# HeadNode_V2.net
KiCad netlist of a schematic drawn in EAGLE
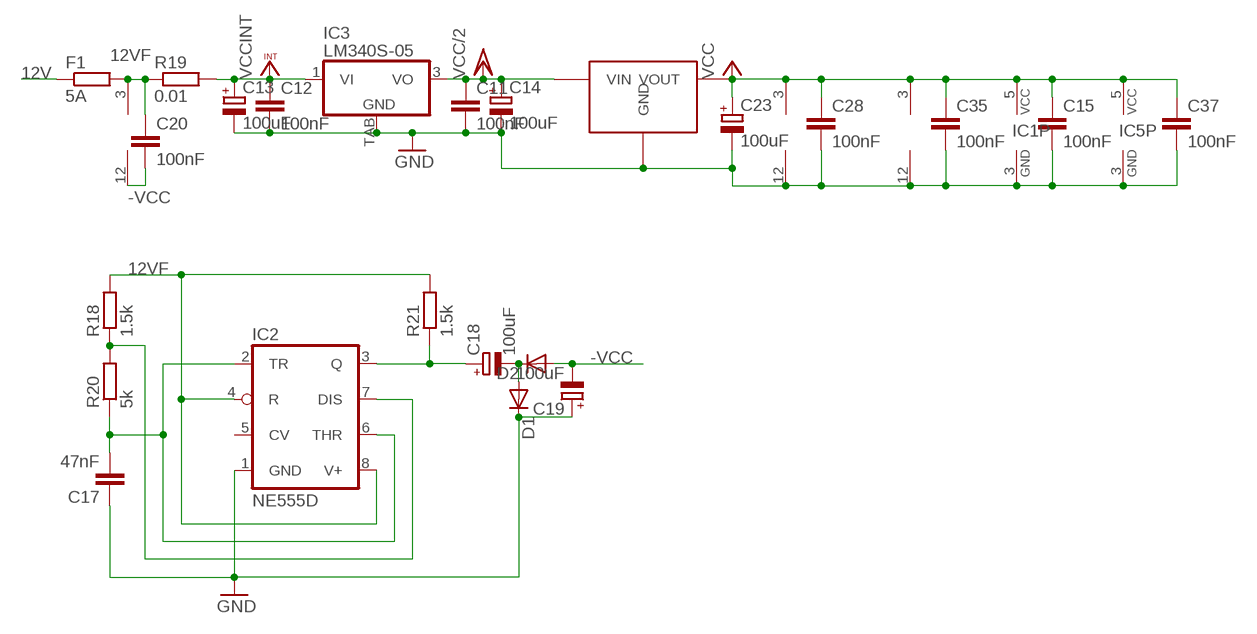
[diagram p0: schematic, sheet 1]
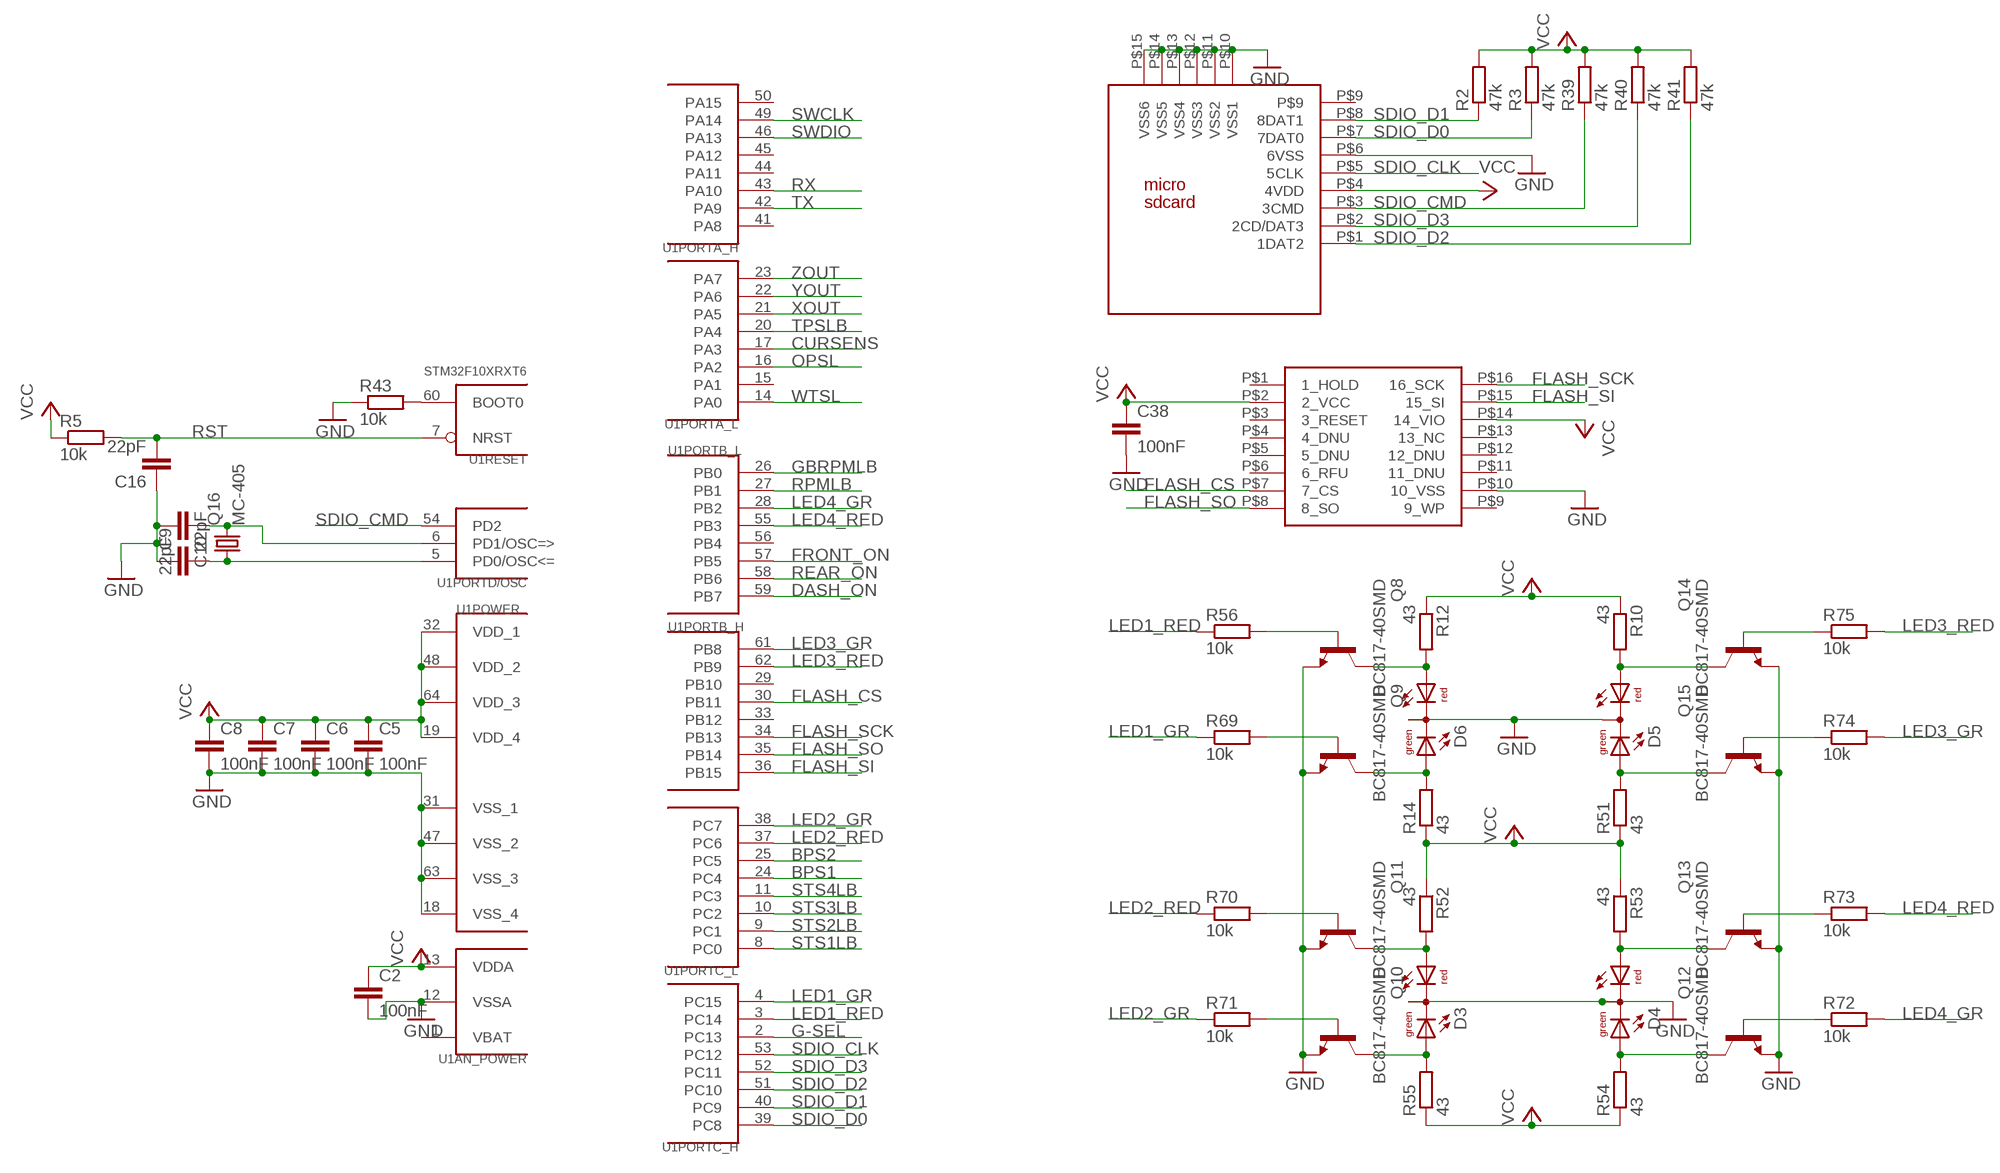
[diagram p1: schematic, sheet 2]
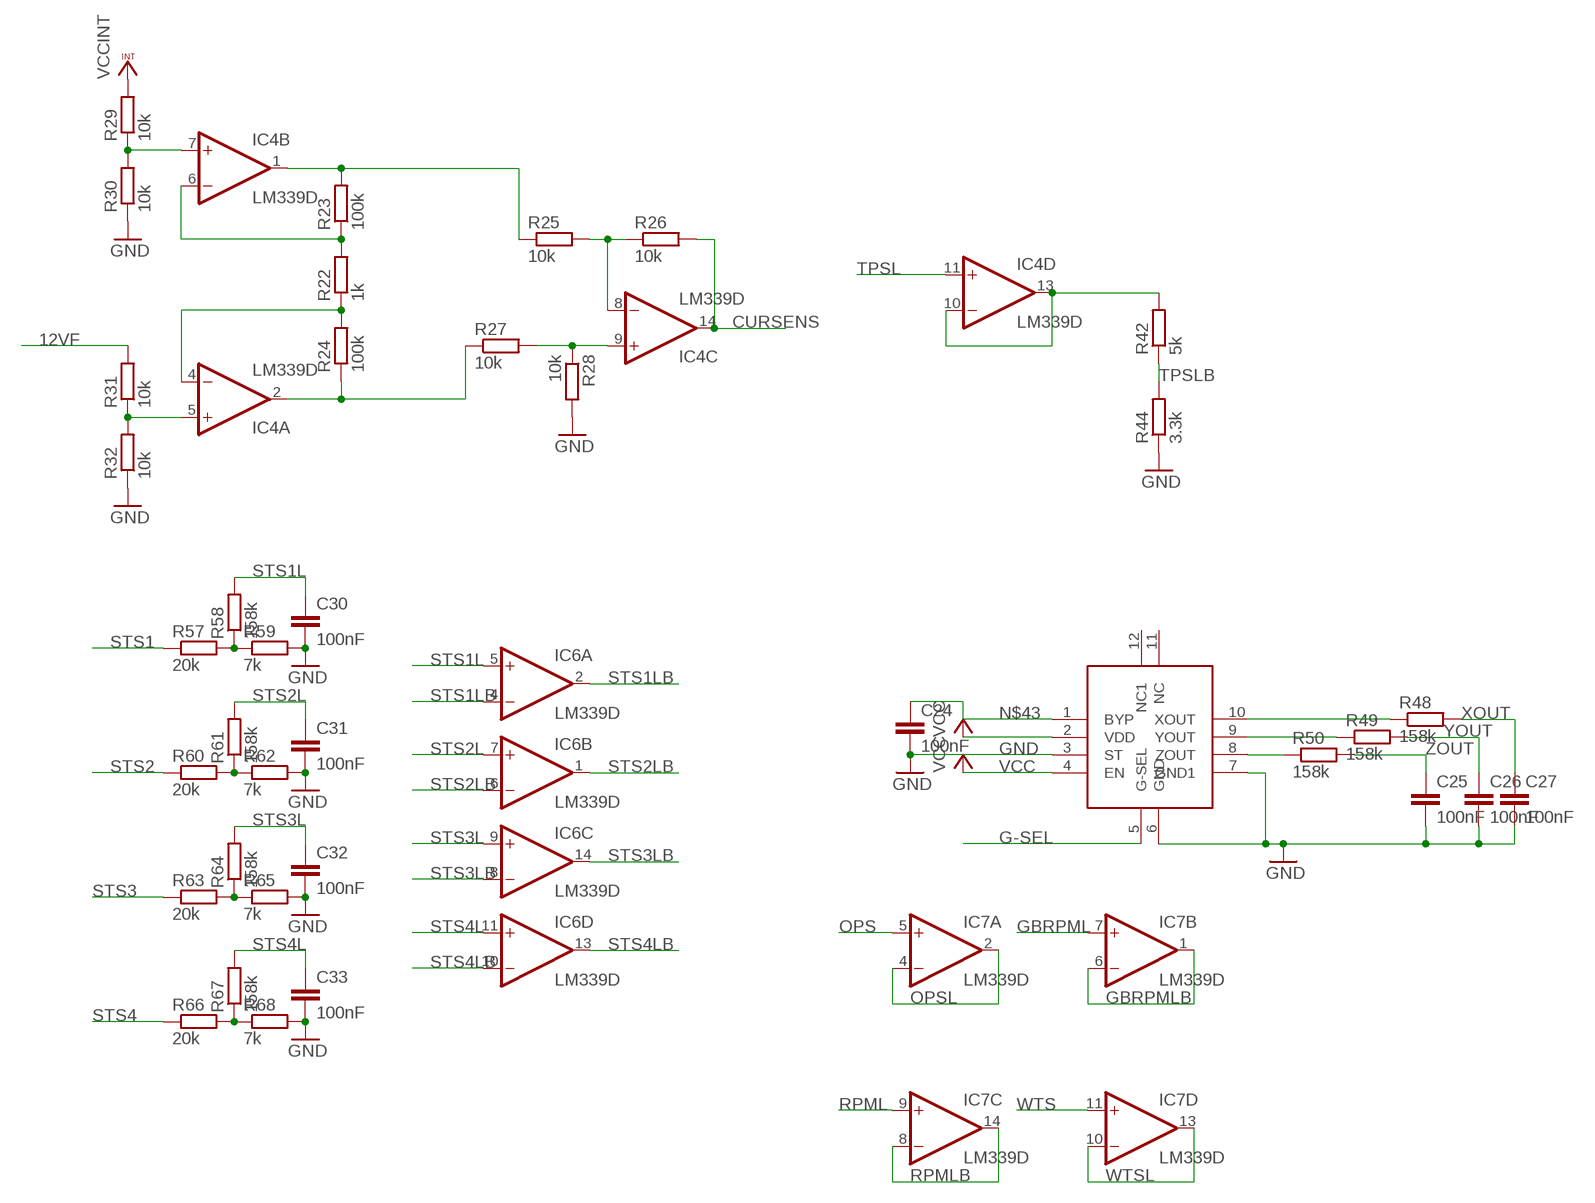
[diagram p2: schematic, sheet 3]
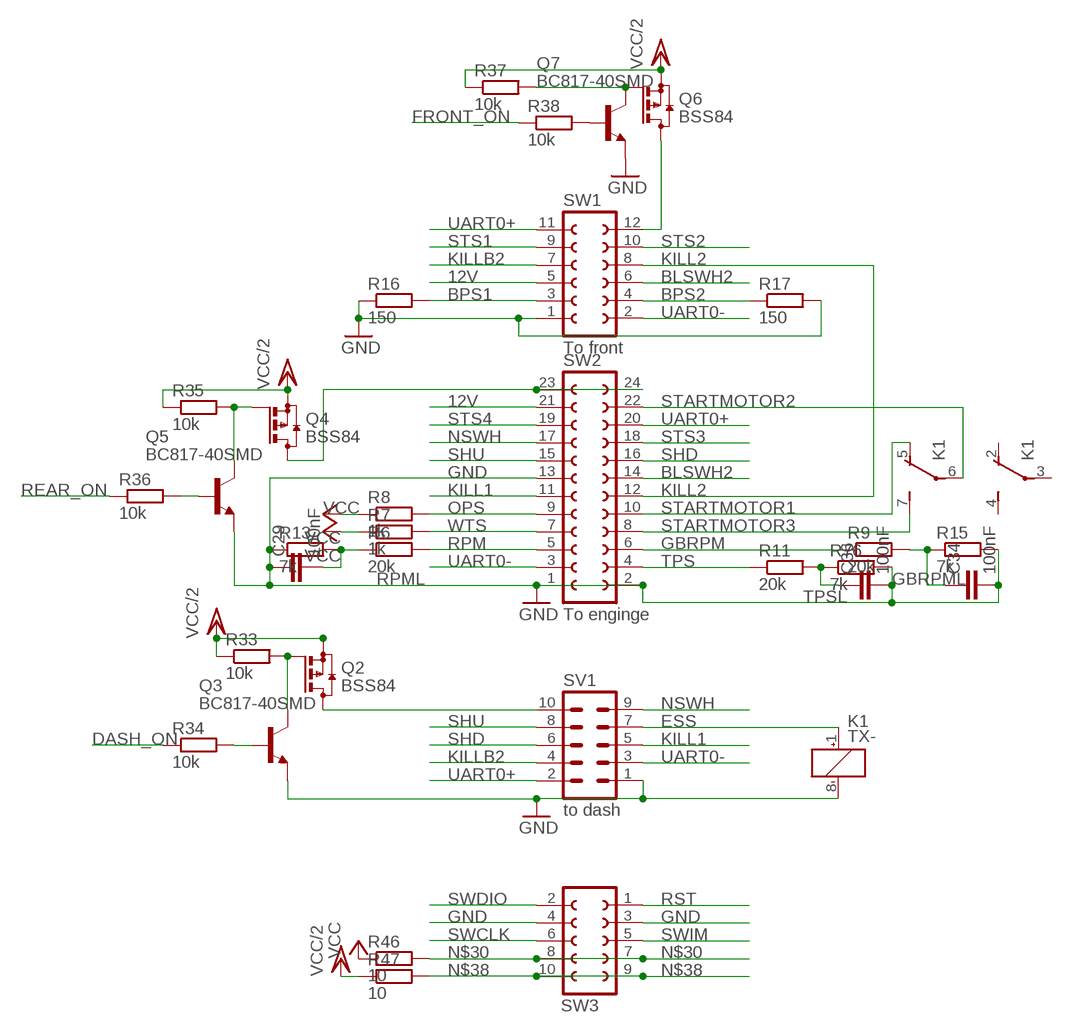
[diagram p3: schematic, sheet 4]
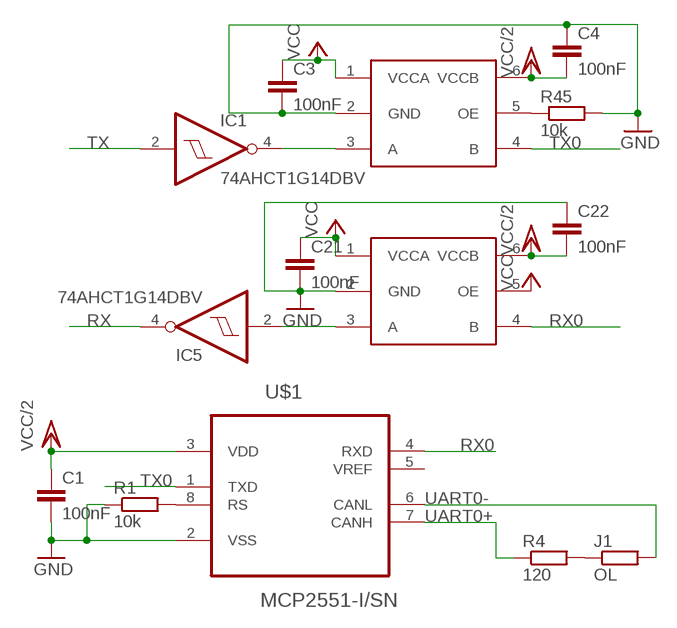
[diagram p4: schematic, sheet 5]

(export (version "E")
  (design (tool "Eeschema 10.0.6"))
  (components
    (comp (ref "C29")
      (value "100nF")
      (footprint "eagle-import:C0805")
      (libsource (lib "eagle-import") (part "C-EUC0805"))
    )
    (comp (ref "C34")
      (value "100nF")
      (footprint "eagle-import:C0805")
      (libsource (lib "eagle-import") (part "C-EUC0805"))
    )
    (comp (ref "C36")
      (value "100nF")
      (footprint "eagle-import:C0805")
      (libsource (lib "eagle-import") (part "C-EUC0805"))
    )
    (comp (ref "K1")
      (value "TX-")
      (footprint "eagle-import:AGQ")
      (fields (field (name "FARNELL") "AGQ210A4HZJ"))
      (libsource (lib "eagle-import") (part "TX?-"))
    )
    (comp (ref "Q2")
      (value "BSS84")
      (footprint "eagle-import:SOT23")
      (libsource (lib "eagle-import") (part "BSS84"))
    )
    (comp (ref "Q3")
      (value "BC817-40SMD")
      (footprint "eagle-import:SOT23-BEC")
      (libsource (lib "eagle-import") (part "BC817SMD-40"))
    )
    (comp (ref "Q4")
      (value "BSS84")
      (footprint "eagle-import:SOT23")
      (libsource (lib "eagle-import") (part "BSS84"))
    )
    (comp (ref "Q5")
      (value "BC817-40SMD")
      (footprint "eagle-import:SOT23-BEC")
      (libsource (lib "eagle-import") (part "BC817SMD-40"))
    )
    (comp (ref "Q6")
      (value "BSS84")
      (footprint "eagle-import:SOT23")
      (libsource (lib "eagle-import") (part "BSS84"))
    )
    (comp (ref "Q7")
      (value "BC817-40SMD")
      (footprint "eagle-import:SOT23-BEC")
      (libsource (lib "eagle-import") (part "BC817SMD-40"))
    )
    (comp (ref "R6")
      (value "20k")
      (footprint "eagle-import:R0805")
      (libsource (lib "eagle-import") (part "R-EU_R0805"))
    )
    (comp (ref "R7")
      (value "1k")
      (footprint "eagle-import:R0805")
      (libsource (lib "eagle-import") (part "R-EU_R0805"))
    )
    (comp (ref "R8")
      (value "1k")
      (footprint "eagle-import:R0805")
      (libsource (lib "eagle-import") (part "R-EU_R0805"))
    )
    (comp (ref "R9")
      (value "20k")
      (footprint "eagle-import:R0805")
      (libsource (lib "eagle-import") (part "R-EU_R0805"))
    )
    (comp (ref "R11")
      (value "20k")
      (footprint "eagle-import:R0805")
      (libsource (lib "eagle-import") (part "R-EU_R0805"))
    )
    (comp (ref "R13")
      (value "7k")
      (footprint "eagle-import:R0805")
      (libsource (lib "eagle-import") (part "R-EU_R0805"))
    )
    (comp (ref "R15")
      (value "7k")
      (footprint "eagle-import:R0805")
      (libsource (lib "eagle-import") (part "R-EU_R0805"))
    )
    (comp (ref "R16")
      (value "150")
      (footprint "eagle-import:R0805")
      (libsource (lib "eagle-import") (part "R-EU_R0805"))
    )
    (comp (ref "R17")
      (value "150")
      (footprint "eagle-import:R0805")
      (libsource (lib "eagle-import") (part "R-EU_R0805"))
    )
    (comp (ref "R33")
      (value "10k")
      (footprint "eagle-import:R0805")
      (libsource (lib "eagle-import") (part "R-EU_R0805"))
    )
    (comp (ref "R34")
      (value "10k")
      (footprint "eagle-import:R0805")
      (libsource (lib "eagle-import") (part "R-EU_R0805"))
    )
    (comp (ref "R35")
      (value "10k")
      (footprint "eagle-import:R0805")
      (libsource (lib "eagle-import") (part "R-EU_R0805"))
    )
    (comp (ref "R36")
      (value "10k")
      (footprint "eagle-import:R0805")
      (libsource (lib "eagle-import") (part "R-EU_R0805"))
    )
    (comp (ref "R37")
      (value "10k")
      (footprint "eagle-import:R0805")
      (libsource (lib "eagle-import") (part "R-EU_R0805"))
    )
    (comp (ref "R38")
      (value "10k")
      (footprint "eagle-import:R0805")
      (libsource (lib "eagle-import") (part "R-EU_R0805"))
    )
    (comp (ref "R46")
      (value "10")
      (footprint "eagle-import:R0805")
      (libsource (lib "eagle-import") (part "R-EU_R0805"))
    )
    (comp (ref "R47")
      (value "10")
      (footprint "eagle-import:R0805")
      (libsource (lib "eagle-import") (part "R-EU_R0805"))
    )
    (comp (ref "R76")
      (value "7k")
      (footprint "eagle-import:R0805")
      (libsource (lib "eagle-import") (part "R-EU_R0805"))
    )
    (comp (ref "SV1")
      (value "to dash")
      (footprint "eagle-import:MA05-2")
      (libsource (lib "eagle-import") (part "MA05-2"))
    )
    (comp (ref "SW1")
      (value "To front")
      (footprint "eagle-import:FE06-2")
      (libsource (lib "eagle-import") (part "FE06-2"))
    )
    (comp (ref "SW2")
      (value "To enginge")
      (footprint "eagle-import:FE12-2")
      (libsource (lib "eagle-import") (part "FE12-2"))
    )
    (comp (ref "SW3")
      (value "To front")
      (footprint "eagle-import:FE05-2W")
      (libsource (lib "eagle-import") (part "FE05-2W"))
    )
    (comp (ref "C11")
      (value "100nF")
      (footprint "eagle-import:C0805")
      (libsource (lib "eagle-import") (part "C-EUC0805"))
    )
    (comp (ref "C12")
      (value "100nF")
      (footprint "eagle-import:C0805")
      (libsource (lib "eagle-import") (part "C-EUC0805"))
    )
    (comp (ref "C13")
      (value "100uF")
      (footprint "eagle-import:153CLV-0605")
      (libsource (lib "eagle-import") (part "CPOL-EU153CLV-0605"))
    )
    (comp (ref "C14")
      (value "100uF")
      (footprint "eagle-import:153CLV-0605")
      (libsource (lib "eagle-import") (part "CPOL-EU153CLV-0605"))
    )
    (comp (ref "C15")
      (value "100nF")
      (footprint "eagle-import:C0805")
      (libsource (lib "eagle-import") (part "C-EUC0805"))
    )
    (comp (ref "C17")
      (value "47nF")
      (footprint "eagle-import:C0805")
      (libsource (lib "eagle-import") (part "C-EUC0805"))
    )
    (comp (ref "C18")
      (value "100uF")
      (footprint "eagle-import:PANASONIC_D")
      (libsource (lib "eagle-import") (part "CPOL-EUD"))
    )
    (comp (ref "C19")
      (value "100uF")
      (footprint "eagle-import:PANASONIC_D")
      (libsource (lib "eagle-import") (part "CPOL-EUD"))
    )
    (comp (ref "C20")
      (value "100nF")
      (footprint "eagle-import:C0805")
      (libsource (lib "eagle-import") (part "C-EUC0805"))
    )
    (comp (ref "C23")
      (value "100uF")
      (footprint "eagle-import:153CLV-0605")
      (libsource (lib "eagle-import") (part "CPOL-EU153CLV-0605"))
    )
    (comp (ref "C28")
      (value "100nF")
      (footprint "eagle-import:C0805")
      (libsource (lib "eagle-import") (part "C-EUC0805"))
    )
    (comp (ref "C35")
      (value "100nF")
      (footprint "eagle-import:C0805")
      (libsource (lib "eagle-import") (part "C-EUC0805"))
    )
    (comp (ref "C37")
      (value "100nF")
      (footprint "eagle-import:C0805")
      (libsource (lib "eagle-import") (part "C-EUC0805"))
    )
    (comp (ref "D1")
      (value "DIODE-DO214AA")
      (footprint "eagle-import:DO214AA")
      (libsource (lib "eagle-import") (part "DIODE-DO214AA"))
    )
    (comp (ref "D2")
      (value "DIODE-DO214AA")
      (footprint "eagle-import:DO214AA")
      (libsource (lib "eagle-import") (part "DIODE-DO214AA"))
    )
    (comp (ref "F1")
      (value "5A")
      (footprint "eagle-import:R1206")
      (libsource (lib "eagle-import") (part "resistor_R-EU_R1206"))
    )
    (comp (ref "IC1")
      (value "74AHCT1G14DBV")
      (footprint "eagle-import:SOT23-5")
      (libsource (lib "eagle-import") (part "741G14DBVAHCT"))
    )
    (comp (ref "IC2")
      (value "NE555D")
      (footprint "eagle-import:SO08")
      (libsource (lib "eagle-import") (part "555DNE"))
    )
    (comp (ref "IC3")
      (value "LM340S-05")
      (footprint "eagle-import:TO263-3")
      (libsource (lib "eagle-import") (part "LM340?-S05"))
    )
    (comp (ref "IC4")
      (value "LM339D")
      (footprint "eagle-import:SO14")
      (libsource (lib "eagle-import") (part "LM339D"))
    )
    (comp (ref "IC5")
      (value "74AHCT1G14DBV")
      (footprint "eagle-import:SOT23-5")
      (libsource (lib "eagle-import") (part "741G14DBVAHCT"))
    )
    (comp (ref "IC6")
      (value "LM339D")
      (footprint "eagle-import:SO14")
      (libsource (lib "eagle-import") (part "LM339D"))
    )
    (comp (ref "IC7")
      (value "LM339D")
      (footprint "eagle-import:SO14")
      (libsource (lib "eagle-import") (part "LM339D"))
    )
    (comp (ref "R18")
      (value "1.5k")
      (footprint "eagle-import:R0805")
      (libsource (lib "eagle-import") (part "R-EU_R0805"))
    )
    (comp (ref "R19")
      (value "0.01")
      (footprint "eagle-import:R4527")
      (libsource (lib "eagle-import") (part "R-EU_R4527"))
    )
    (comp (ref "R20")
      (value "5k")
      (footprint "eagle-import:R0805")
      (libsource (lib "eagle-import") (part "R-EU_R0805"))
    )
    (comp (ref "R21")
      (value "1.5k")
      (footprint "eagle-import:R0805")
      (libsource (lib "eagle-import") (part "R-EU_R0805"))
    )
    (comp (ref "U$5")
      (value "TS2940")
      (footprint "eagle-import:TO-252")
      (libsource (lib "eagle-import") (part "TS2940"))
    )
    (comp (ref "C2")
      (value "100nF")
      (footprint "eagle-import:C0805")
      (libsource (lib "eagle-import") (part "C-EUC0805"))
    )
    (comp (ref "C5")
      (value "100nF")
      (footprint "eagle-import:C0805")
      (libsource (lib "eagle-import") (part "C-EUC0805"))
    )
    (comp (ref "C6")
      (value "100nF")
      (footprint "eagle-import:C0805")
      (libsource (lib "eagle-import") (part "C-EUC0805"))
    )
    (comp (ref "C7")
      (value "100nF")
      (footprint "eagle-import:C0805")
      (libsource (lib "eagle-import") (part "C-EUC0805"))
    )
    (comp (ref "C8")
      (value "100nF")
      (footprint "eagle-import:C0805")
      (libsource (lib "eagle-import") (part "C-EUC0805"))
    )
    (comp (ref "C9")
      (value "22pF")
      (footprint "eagle-import:C0805")
      (libsource (lib "eagle-import") (part "C-EUC0805"))
    )
    (comp (ref "C10")
      (value "22pF")
      (footprint "eagle-import:C0805")
      (libsource (lib "eagle-import") (part "C-EUC0805"))
    )
    (comp (ref "C16")
      (value "22pF")
      (footprint "eagle-import:C0805")
      (libsource (lib "eagle-import") (part "C-EUC0805"))
    )
    (comp (ref "C38")
      (value "100nF")
      (footprint "eagle-import:C0805")
      (libsource (lib "eagle-import") (part "C-EUC0805"))
    )
    (comp (ref "D3")
      (value "DUOLED5MM")
      (footprint "eagle-import:DUOLED5MM")
      (libsource (lib "eagle-import") (part "DUOLED5MM"))
    )
    (comp (ref "D4")
      (value "DUOLED5MM")
      (footprint "eagle-import:DUOLED5MM")
      (libsource (lib "eagle-import") (part "DUOLED5MM"))
    )
    (comp (ref "D5")
      (value "DUOLED5MM")
      (footprint "eagle-import:DUOLED5MM")
      (libsource (lib "eagle-import") (part "DUOLED5MM"))
    )
    (comp (ref "D6")
      (value "DUOLED5MM")
      (footprint "eagle-import:DUOLED5MM")
      (libsource (lib "eagle-import") (part "DUOLED5MM"))
    )
    (comp (ref "Q8")
      (value "BC817-40SMD")
      (footprint "eagle-import:SOT23-BEC")
      (libsource (lib "eagle-import") (part "BC817SMD-40"))
    )
    (comp (ref "Q9")
      (value "BC817-40SMD")
      (footprint "eagle-import:SOT23-BEC")
      (libsource (lib "eagle-import") (part "BC817SMD-40"))
    )
    (comp (ref "Q10")
      (value "BC817-40SMD")
      (footprint "eagle-import:SOT23-BEC")
      (libsource (lib "eagle-import") (part "BC817SMD-40"))
    )
    (comp (ref "Q11")
      (value "BC817-40SMD")
      (footprint "eagle-import:SOT23-BEC")
      (libsource (lib "eagle-import") (part "BC817SMD-40"))
    )
    (comp (ref "Q12")
      (value "BC817-40SMD")
      (footprint "eagle-import:SOT23-BEC")
      (libsource (lib "eagle-import") (part "BC817SMD-40"))
    )
    (comp (ref "Q13")
      (value "BC817-40SMD")
      (footprint "eagle-import:SOT23-BEC")
      (libsource (lib "eagle-import") (part "BC817SMD-40"))
    )
    (comp (ref "Q14")
      (value "BC817-40SMD")
      (footprint "eagle-import:SOT23-BEC")
      (libsource (lib "eagle-import") (part "BC817SMD-40"))
    )
    (comp (ref "Q15")
      (value "BC817-40SMD")
      (footprint "eagle-import:SOT23-BEC")
      (libsource (lib "eagle-import") (part "BC817SMD-40"))
    )
    (comp (ref "Q16")
      (value "MC-405")
      (footprint "eagle-import:MC-405")
      (libsource (lib "eagle-import") (part "MC-405"))
    )
    (comp (ref "R2")
      (value "47k")
      (footprint "eagle-import:R0805")
      (libsource (lib "eagle-import") (part "R-EU_R0805"))
    )
    (comp (ref "R3")
      (value "47k")
      (footprint "eagle-import:R0805")
      (libsource (lib "eagle-import") (part "R-EU_R0805"))
    )
    (comp (ref "R5")
      (value "10k")
      (footprint "eagle-import:M0805")
      (libsource (lib "eagle-import") (part "resistor_R-EU_M0805"))
    )
    (comp (ref "R10")
      (value "43")
      (footprint "eagle-import:R0805")
      (libsource (lib "eagle-import") (part "R-EU_R0805"))
    )
    (comp (ref "R12")
      (value "43")
      (footprint "eagle-import:R0805")
      (libsource (lib "eagle-import") (part "R-EU_R0805"))
    )
    (comp (ref "R14")
      (value "43")
      (footprint "eagle-import:R0805")
      (libsource (lib "eagle-import") (part "R-EU_R0805"))
    )
    (comp (ref "R39")
      (value "47k")
      (footprint "eagle-import:R0805")
      (libsource (lib "eagle-import") (part "R-EU_R0805"))
    )
    (comp (ref "R40")
      (value "47k")
      (footprint "eagle-import:R0805")
      (libsource (lib "eagle-import") (part "R-EU_R0805"))
    )
    (comp (ref "R41")
      (value "47k")
      (footprint "eagle-import:R0805")
      (libsource (lib "eagle-import") (part "R-EU_R0805"))
    )
    (comp (ref "R43")
      (value "10k")
      (footprint "eagle-import:M0805")
      (libsource (lib "eagle-import") (part "resistor_R-EU_M0805"))
    )
    (comp (ref "R51")
      (value "43")
      (footprint "eagle-import:R0805")
      (libsource (lib "eagle-import") (part "R-EU_R0805"))
    )
    (comp (ref "R52")
      (value "43")
      (footprint "eagle-import:R0805")
      (libsource (lib "eagle-import") (part "R-EU_R0805"))
    )
    (comp (ref "R53")
      (value "43")
      (footprint "eagle-import:R0805")
      (libsource (lib "eagle-import") (part "R-EU_R0805"))
    )
    (comp (ref "R54")
      (value "43")
      (footprint "eagle-import:R0805")
      (libsource (lib "eagle-import") (part "R-EU_R0805"))
    )
    (comp (ref "R55")
      (value "43")
      (footprint "eagle-import:R0805")
      (libsource (lib "eagle-import") (part "R-EU_R0805"))
    )
    (comp (ref "R56")
      (value "10k")
      (footprint "eagle-import:R0805")
      (libsource (lib "eagle-import") (part "R-EU_R0805"))
    )
    (comp (ref "R69")
      (value "10k")
      (footprint "eagle-import:R0805")
      (libsource (lib "eagle-import") (part "R-EU_R0805"))
    )
    (comp (ref "R70")
      (value "10k")
      (footprint "eagle-import:R0805")
      (libsource (lib "eagle-import") (part "R-EU_R0805"))
    )
    (comp (ref "R71")
      (value "10k")
      (footprint "eagle-import:R0805")
      (libsource (lib "eagle-import") (part "R-EU_R0805"))
    )
    (comp (ref "R72")
      (value "10k")
      (footprint "eagle-import:R0805")
      (libsource (lib "eagle-import") (part "R-EU_R0805"))
    )
    (comp (ref "R73")
      (value "10k")
      (footprint "eagle-import:R0805")
      (libsource (lib "eagle-import") (part "R-EU_R0805"))
    )
    (comp (ref "R74")
      (value "10k")
      (footprint "eagle-import:R0805")
      (libsource (lib "eagle-import") (part "R-EU_R0805"))
    )
    (comp (ref "R75")
      (value "10k")
      (footprint "eagle-import:R0805")
      (libsource (lib "eagle-import") (part "R-EU_R0805"))
    )
    (comp (ref "U$2")
      (value "MICRO")
      (footprint "eagle-import:MICRO")
      (libsource (lib "eagle-import") (part "MICRO"))
    )
    (comp (ref "U$7")
      (value "S25FL512SAGMFIG11")
      (footprint "eagle-import:16SOIC")
      (libsource (lib "eagle-import") (part "S25FL512SAGMFIG11"))
    )
    (comp (ref "U1")
      (value "STM32F10XRXT6")
      (footprint "eagle-import:TQFP64")
      (libsource (lib "eagle-import") (part "STM32F10XRXT6"))
    )
    (comp (ref "C1")
      (value "100nF")
      (footprint "eagle-import:C0805")
      (libsource (lib "eagle-import") (part "C-EUC0805"))
    )
    (comp (ref "C3")
      (value "100nF")
      (footprint "eagle-import:C0805")
      (libsource (lib "eagle-import") (part "C-EUC0805"))
    )
    (comp (ref "C4")
      (value "100nF")
      (footprint "eagle-import:C0805")
      (libsource (lib "eagle-import") (part "C-EUC0805"))
    )
    (comp (ref "C21")
      (value "100nF")
      (footprint "eagle-import:C0805")
      (libsource (lib "eagle-import") (part "C-EUC0805"))
    )
    (comp (ref "C22")
      (value "100nF")
      (footprint "eagle-import:C0805")
      (libsource (lib "eagle-import") (part "C-EUC0805"))
    )
    (comp (ref "J1")
      (value "OL")
      (footprint "eagle-import:R0805")
      (libsource (lib "eagle-import") (part "R-EU_R0805"))
    )
    (comp (ref "R1")
      (value "10k")
      (footprint "eagle-import:M0805")
      (libsource (lib "eagle-import") (part "resistor_R-EU_M0805"))
    )
    (comp (ref "R4")
      (value "120")
      (footprint "eagle-import:R0805")
      (libsource (lib "eagle-import") (part "R-EU_R0805"))
    )
    (comp (ref "R45")
      (value "10k")
      (footprint "eagle-import:R0805")
      (libsource (lib "eagle-import") (part "R-EU_R0805"))
    )
    (comp (ref "U$1")
      (value "MCP2551-I/SN")
      (footprint "eagle-import:SOIC127P600X175-8N")
      (libsource (lib "eagle-import") (part "MCP2551-I/SN"))
    )
    (comp (ref "U$3")
      (value "TXB0101")
      (footprint "eagle-import:TSOT23-6_DDC")
      (libsource (lib "eagle-import") (part "TXB0101"))
    )
    (comp (ref "U$4")
      (value "TXB0101")
      (footprint "eagle-import:TSOT23-6_DDC")
      (libsource (lib "eagle-import") (part "TXB0101"))
    )
    (comp (ref "C24")
      (value "100nF")
      (footprint "eagle-import:C0805")
      (libsource (lib "eagle-import") (part "C-EUC0805"))
    )
    (comp (ref "C25")
      (value "100nF")
      (footprint "eagle-import:C0805")
      (libsource (lib "eagle-import") (part "C-EUC0805"))
    )
    (comp (ref "C26")
      (value "100nF")
      (footprint "eagle-import:C0805")
      (libsource (lib "eagle-import") (part "C-EUC0805"))
    )
    (comp (ref "C27")
      (value "100nF")
      (footprint "eagle-import:C0805")
      (libsource (lib "eagle-import") (part "C-EUC0805"))
    )
    (comp (ref "C30")
      (value "100nF")
      (footprint "eagle-import:C0805")
      (libsource (lib "eagle-import") (part "C-EUC0805"))
    )
    (comp (ref "C31")
      (value "100nF")
      (footprint "eagle-import:C0805")
      (libsource (lib "eagle-import") (part "C-EUC0805"))
    )
    (comp (ref "C32")
      (value "100nF")
      (footprint "eagle-import:C0805")
      (libsource (lib "eagle-import") (part "C-EUC0805"))
    )
    (comp (ref "C33")
      (value "100nF")
      (footprint "eagle-import:C0805")
      (libsource (lib "eagle-import") (part "C-EUC0805"))
    )
    (comp (ref "R22")
      (value "1k")
      (footprint "eagle-import:M0805")
      (libsource (lib "eagle-import") (part "resistor_R-EU_M0805"))
    )
    (comp (ref "R23")
      (value "100k")
      (footprint "eagle-import:M0805")
      (libsource (lib "eagle-import") (part "resistor_R-EU_M0805"))
    )
    (comp (ref "R24")
      (value "100k")
      (footprint "eagle-import:M0805")
      (libsource (lib "eagle-import") (part "resistor_R-EU_M0805"))
    )
    (comp (ref "R25")
      (value "10k")
      (footprint "eagle-import:M0805")
      (libsource (lib "eagle-import") (part "resistor_R-EU_M0805"))
    )
    (comp (ref "R26")
      (value "10k")
      (footprint "eagle-import:M0805")
      (libsource (lib "eagle-import") (part "resistor_R-EU_M0805"))
    )
    (comp (ref "R27")
      (value "10k")
      (footprint "eagle-import:M0805")
      (libsource (lib "eagle-import") (part "resistor_R-EU_M0805"))
    )
    (comp (ref "R28")
      (value "10k")
      (footprint "eagle-import:M0805")
      (libsource (lib "eagle-import") (part "resistor_R-EU_M0805"))
    )
    (comp (ref "R29")
      (value "10k")
      (footprint "eagle-import:M0805")
      (libsource (lib "eagle-import") (part "resistor_R-EU_M0805"))
    )
    (comp (ref "R30")
      (value "10k")
      (footprint "eagle-import:M0805")
      (libsource (lib "eagle-import") (part "resistor_R-EU_M0805"))
    )
    (comp (ref "R31")
      (value "10k")
      (footprint "eagle-import:M0805")
      (libsource (lib "eagle-import") (part "resistor_R-EU_M0805"))
    )
    (comp (ref "R32")
      (value "10k")
      (footprint "eagle-import:M0805")
      (libsource (lib "eagle-import") (part "resistor_R-EU_M0805"))
    )
    (comp (ref "R42")
      (value "5k")
      (footprint "eagle-import:R0805")
      (libsource (lib "eagle-import") (part "R-EU_R0805"))
    )
    (comp (ref "R44")
      (value "3.3k")
      (footprint "eagle-import:R0805")
      (libsource (lib "eagle-import") (part "R-EU_R0805"))
    )
    (comp (ref "R48")
      (value "158k")
      (footprint "eagle-import:R0805")
      (libsource (lib "eagle-import") (part "R-EU_R0805"))
    )
    (comp (ref "R49")
      (value "158k")
      (footprint "eagle-import:R0805")
      (libsource (lib "eagle-import") (part "R-EU_R0805"))
    )
    (comp (ref "R50")
      (value "158k")
      (footprint "eagle-import:R0805")
      (libsource (lib "eagle-import") (part "R-EU_R0805"))
    )
    (comp (ref "R57")
      (value "20k")
      (footprint "eagle-import:R0805")
      (libsource (lib "eagle-import") (part "R-EU_R0805"))
    )
    (comp (ref "R58")
      (value "158k")
      (footprint "eagle-import:R0805")
      (libsource (lib "eagle-import") (part "R-EU_R0805"))
    )
    (comp (ref "R59")
      (value "7k")
      (footprint "eagle-import:R0805")
      (libsource (lib "eagle-import") (part "R-EU_R0805"))
    )
    (comp (ref "R60")
      (value "20k")
      (footprint "eagle-import:R0805")
      (libsource (lib "eagle-import") (part "R-EU_R0805"))
    )
    (comp (ref "R61")
      (value "158k")
      (footprint "eagle-import:R0805")
      (libsource (lib "eagle-import") (part "R-EU_R0805"))
    )
    (comp (ref "R62")
      (value "7k")
      (footprint "eagle-import:R0805")
      (libsource (lib "eagle-import") (part "R-EU_R0805"))
    )
    (comp (ref "R63")
      (value "20k")
      (footprint "eagle-import:R0805")
      (libsource (lib "eagle-import") (part "R-EU_R0805"))
    )
    (comp (ref "R64")
      (value "158k")
      (footprint "eagle-import:R0805")
      (libsource (lib "eagle-import") (part "R-EU_R0805"))
    )
    (comp (ref "R65")
      (value "7k")
      (footprint "eagle-import:R0805")
      (libsource (lib "eagle-import") (part "R-EU_R0805"))
    )
    (comp (ref "R66")
      (value "20k")
      (footprint "eagle-import:R0805")
      (libsource (lib "eagle-import") (part "R-EU_R0805"))
    )
    (comp (ref "R67")
      (value "158k")
      (footprint "eagle-import:R0805")
      (libsource (lib "eagle-import") (part "R-EU_R0805"))
    )
    (comp (ref "R68")
      (value "7k")
      (footprint "eagle-import:R0805")
      (libsource (lib "eagle-import") (part "R-EU_R0805"))
    )
    (comp (ref "U$6")
      (value "FXLN8371QR1")
      (footprint "eagle-import:QFN")
      (libsource (lib "eagle-import") (part "FXLN8371QR1"))
    )
  )
  (nets
    (net (code "1") (name "-VCC") (class "Default")
      (node (ref "C19") (pin "-") (pinfunction "-_-") (pintype "passive"))
      (node (ref "C20") (pin "2") (pinfunction "2_2") (pintype "passive"))
      (node (ref "D2") (pin "A") (pinfunction "A_A") (pintype "passive"))
      (node (ref "IC4") (pin "12") (pinfunction "GND_12") (pintype "power_in"))
    )
    (net (code "2") (name "12V") (class "Default")
      (node (ref "F1") (pin "1") (pinfunction "1_1") (pintype "passive"))
      (node (ref "SW1") (pin "5") (pinfunction "5_5") (pintype "passive"))
      (node (ref "SW2") (pin "21") (pinfunction "21_21") (pintype "passive"))
    )
    (net (code "3") (name "12VF") (class "Default")
      (node (ref "C20") (pin "1") (pinfunction "1_1") (pintype "passive"))
      (node (ref "F1") (pin "2") (pinfunction "2_2") (pintype "passive"))
      (node (ref "IC2") (pin "4") (pinfunction "R_4") (pintype "input"))
      (node (ref "IC2") (pin "8") (pinfunction "V+_8") (pintype "power_in"))
      (node (ref "IC4") (pin "3") (pinfunction "V+_3") (pintype "power_in"))
      (node (ref "R18") (pin "2") (pinfunction "2_2") (pintype "passive"))
      (node (ref "R19") (pin "1") (pinfunction "1_1") (pintype "passive"))
      (node (ref "R21") (pin "2") (pinfunction "2_2") (pintype "passive"))
      (node (ref "R31") (pin "2") (pinfunction "2_2") (pintype "passive"))
    )
    (net (code "4") (name "BLSWH2") (class "Default")
      (node (ref "SW1") (pin "6") (pinfunction "6_6") (pintype "passive"))
      (node (ref "SW2") (pin "14") (pinfunction "14_14") (pintype "passive"))
    )
    (net (code "5") (name "BPS1") (class "Default")
      (node (ref "R16") (pin "2") (pinfunction "2_2") (pintype "passive"))
      (node (ref "SW1") (pin "3") (pinfunction "3_3") (pintype "passive"))
      (node (ref "U1") (pin "24") (pinfunction "PC4_24") (pintype "bidirectional"))
    )
    (net (code "6") (name "BPS2") (class "Default")
      (node (ref "R17") (pin "1") (pinfunction "1_1") (pintype "passive"))
      (node (ref "SW1") (pin "4") (pinfunction "4_4") (pintype "passive"))
      (node (ref "U1") (pin "25") (pinfunction "PC5_25") (pintype "bidirectional"))
    )
    (net (code "7") (name "CURSENS") (class "Default")
      (node (ref "IC4") (pin "14") (pinfunction "OUT_14") (pintype "open_collector"))
      (node (ref "R26") (pin "2") (pinfunction "2_2") (pintype "passive"))
      (node (ref "U1") (pin "17") (pinfunction "PA3_17") (pintype "bidirectional"))
    )
    (net (code "8") (name "DASH_ON") (class "Default")
      (node (ref "R34") (pin "1") (pinfunction "1_1") (pintype "passive"))
      (node (ref "U1") (pin "59") (pinfunction "PB7_59") (pintype "bidirectional"))
    )
    (net (code "9") (name "ESS") (class "Default")
      (node (ref "K1") (pin "1") (pinfunction "+_1") (pintype "passive"))
      (node (ref "SV1") (pin "7") (pinfunction "7_7") (pintype "passive"))
    )
    (net (code "10") (name "FLASH_CS") (class "Default")
      (node (ref "U$7") (pin "P$7") (pinfunction "7_CS_P$7") (pintype "bidirectional"))
      (node (ref "U1") (pin "30") (pinfunction "PB11_30") (pintype "bidirectional"))
    )
    (net (code "11") (name "FLASH_SCK") (class "Default")
      (node (ref "U$7") (pin "P$16") (pinfunction "16_SCK_P$16") (pintype "bidirectional"))
      (node (ref "U1") (pin "34") (pinfunction "PB13_34") (pintype "bidirectional"))
    )
    (net (code "12") (name "FLASH_SI") (class "Default")
      (node (ref "U$7") (pin "P$15") (pinfunction "15_SI_P$15") (pintype "bidirectional"))
      (node (ref "U1") (pin "36") (pinfunction "PB15_36") (pintype "bidirectional"))
    )
    (net (code "13") (name "FLASH_SO") (class "Default")
      (node (ref "U$7") (pin "P$8") (pinfunction "8_SO_P$8") (pintype "bidirectional"))
      (node (ref "U1") (pin "35") (pinfunction "PB14_35") (pintype "bidirectional"))
    )
    (net (code "14") (name "FRONT_ON") (class "Default")
      (node (ref "R38") (pin "1") (pinfunction "1_1") (pintype "passive"))
      (node (ref "U1") (pin "57") (pinfunction "PB5_57") (pintype "bidirectional"))
    )
    (net (code "15") (name "G-SEL") (class "Default")
      (node (ref "U$6") (pin "5") (pinfunction "G-SEL_5") (pintype "bidirectional"))
      (node (ref "U1") (pin "2") (pinfunction "PC13_2") (pintype "bidirectional"))
    )
    (net (code "16") (name "GBRPM") (class "Default")
      (node (ref "R9") (pin "1") (pinfunction "1_1") (pintype "passive"))
      (node (ref "SW2") (pin "6") (pinfunction "6_6") (pintype "passive"))
    )
    (net (code "17") (name "GBRPML") (class "Default")
      (node (ref "C34") (pin "1") (pinfunction "1_1") (pintype "passive"))
      (node (ref "IC7") (pin "7") (pinfunction "+IN_7") (pintype "input"))
      (node (ref "R15") (pin "1") (pinfunction "1_1") (pintype "passive"))
      (node (ref "R9") (pin "2") (pinfunction "2_2") (pintype "passive"))
    )
    (net (code "18") (name "GBRPMLB") (class "Default")
      (node (ref "IC7") (pin "1") (pinfunction "OUT_1") (pintype "open_collector"))
      (node (ref "IC7") (pin "6") (pinfunction "-IN_6") (pintype "input"))
      (node (ref "U1") (pin "26") (pinfunction "PB0_26") (pintype "bidirectional"))
    )
    (net (code "19") (name "GND") (class "Default")
      (node (ref "C1") (pin "2") (pinfunction "2_2") (pintype "passive"))
      (node (ref "C10") (pin "2") (pinfunction "2_2") (pintype "passive"))
      (node (ref "C11") (pin "2") (pinfunction "2_2") (pintype "passive"))
      (node (ref "C12") (pin "2") (pinfunction "2_2") (pintype "passive"))
      (node (ref "C13") (pin "-") (pinfunction "-_-") (pintype "passive"))
      (node (ref "C14") (pin "-") (pinfunction "-_-") (pintype "passive"))
      (node (ref "C15") (pin "2") (pinfunction "2_2") (pintype "passive"))
      (node (ref "C16") (pin "1") (pinfunction "1_1") (pintype "passive"))
      (node (ref "C17") (pin "1") (pinfunction "1_1") (pintype "passive"))
      (node (ref "C19") (pin "+") (pinfunction "+_+") (pintype "passive"))
      (node (ref "C2") (pin "2") (pinfunction "2_2") (pintype "passive"))
      (node (ref "C21") (pin "2") (pinfunction "2_2") (pintype "passive"))
      (node (ref "C22") (pin "1") (pinfunction "1_1") (pintype "passive"))
      (node (ref "C23") (pin "-") (pinfunction "-_-") (pintype "passive"))
      (node (ref "C24") (pin "2") (pinfunction "2_2") (pintype "passive"))
      (node (ref "C25") (pin "2") (pinfunction "2_2") (pintype "passive"))
      (node (ref "C26") (pin "2") (pinfunction "2_2") (pintype "passive"))
      (node (ref "C27") (pin "2") (pinfunction "2_2") (pintype "passive"))
      (node (ref "C28") (pin "2") (pinfunction "2_2") (pintype "passive"))
      (node (ref "C29") (pin "1") (pinfunction "1_1") (pintype "passive"))
      (node (ref "C3") (pin "2") (pinfunction "2_2") (pintype "passive"))
      (node (ref "C30") (pin "2") (pinfunction "2_2") (pintype "passive"))
      (node (ref "C31") (pin "2") (pinfunction "2_2") (pintype "passive"))
      (node (ref "C32") (pin "2") (pinfunction "2_2") (pintype "passive"))
      (node (ref "C33") (pin "2") (pinfunction "2_2") (pintype "passive"))
      (node (ref "C34") (pin "2") (pinfunction "2_2") (pintype "passive"))
      (node (ref "C35") (pin "2") (pinfunction "2_2") (pintype "passive"))
      (node (ref "C36") (pin "2") (pinfunction "2_2") (pintype "passive"))
      (node (ref "C37") (pin "2") (pinfunction "2_2") (pintype "passive"))
      (node (ref "C38") (pin "2") (pinfunction "2_2") (pintype "passive"))
      (node (ref "C4") (pin "1") (pinfunction "1_1") (pintype "passive"))
      (node (ref "C5") (pin "2") (pinfunction "2_2") (pintype "passive"))
      (node (ref "C6") (pin "2") (pinfunction "2_2") (pintype "passive"))
      (node (ref "C7") (pin "2") (pinfunction "2_2") (pintype "passive"))
      (node (ref "C8") (pin "2") (pinfunction "2_2") (pintype "passive"))
      (node (ref "C9") (pin "1") (pinfunction "1_1") (pintype "passive"))
      (node (ref "D1") (pin "C") (pinfunction "C_C") (pintype "passive"))
      (node (ref "D3") (pin "K") (pinfunction "C_K") (pintype "passive"))
      (node (ref "D4") (pin "K") (pinfunction "C_K") (pintype "passive"))
      (node (ref "D5") (pin "K") (pinfunction "C_K") (pintype "passive"))
      (node (ref "D6") (pin "K") (pinfunction "C_K") (pintype "passive"))
      (node (ref "IC1") (pin "3") (pinfunction "GND_3") (pintype "power_in"))
      (node (ref "IC2") (pin "1") (pinfunction "GND_1") (pintype "power_in"))
      (node (ref "IC3") (pin "TAB") (pinfunction "GND_TAB") (pintype "passive"))
      (node (ref "IC5") (pin "3") (pinfunction "GND_3") (pintype "power_in"))
      (node (ref "IC6") (pin "12") (pinfunction "GND_12") (pintype "power_in"))
      (node (ref "IC7") (pin "12") (pinfunction "GND_12") (pintype "power_in"))
      (node (ref "K1") (pin "8") (pinfunction "-_8") (pintype "passive"))
      (node (ref "Q10") (pin "E") (pinfunction "E_E") (pintype "passive"))
      (node (ref "Q11") (pin "E") (pinfunction "E_E") (pintype "passive"))
      (node (ref "Q12") (pin "E") (pinfunction "E_E") (pintype "passive"))
      (node (ref "Q13") (pin "E") (pinfunction "E_E") (pintype "passive"))
      (node (ref "Q14") (pin "E") (pinfunction "E_E") (pintype "passive"))
      (node (ref "Q15") (pin "E") (pinfunction "E_E") (pintype "passive"))
      (node (ref "Q3") (pin "E") (pinfunction "E_E") (pintype "passive"))
      (node (ref "Q5") (pin "E") (pinfunction "E_E") (pintype "passive"))
      (node (ref "Q7") (pin "E") (pinfunction "E_E") (pintype "passive"))
      (node (ref "Q8") (pin "E") (pinfunction "E_E") (pintype "passive"))
      (node (ref "Q9") (pin "E") (pinfunction "E_E") (pintype "passive"))
      (node (ref "R1") (pin "1") (pinfunction "1_1") (pintype "passive"))
      (node (ref "R13") (pin "1") (pinfunction "1_1") (pintype "passive"))
      (node (ref "R15") (pin "2") (pinfunction "2_2") (pintype "passive"))
      (node (ref "R16") (pin "1") (pinfunction "1_1") (pintype "passive"))
      (node (ref "R17") (pin "2") (pinfunction "2_2") (pintype "passive"))
      (node (ref "R28") (pin "2") (pinfunction "2_2") (pintype "passive"))
      (node (ref "R30") (pin "1") (pinfunction "1_1") (pintype "passive"))
      (node (ref "R32") (pin "1") (pinfunction "1_1") (pintype "passive"))
      (node (ref "R43") (pin "1") (pinfunction "1_1") (pintype "passive"))
      (node (ref "R44") (pin "1") (pinfunction "1_1") (pintype "passive"))
      (node (ref "R45") (pin "2") (pinfunction "2_2") (pintype "passive"))
      (node (ref "R59") (pin "2") (pinfunction "2_2") (pintype "passive"))
      (node (ref "R62") (pin "2") (pinfunction "2_2") (pintype "passive"))
      (node (ref "R65") (pin "2") (pinfunction "2_2") (pintype "passive"))
      (node (ref "R68") (pin "2") (pinfunction "2_2") (pintype "passive"))
      (node (ref "R76") (pin "2") (pinfunction "2_2") (pintype "passive"))
      (node (ref "SV1") (pin "1") (pinfunction "1_1") (pintype "passive"))
      (node (ref "SW1") (pin "1") (pinfunction "1_1") (pintype "passive"))
      (node (ref "SW2") (pin "1") (pinfunction "1_1") (pintype "passive"))
      (node (ref "SW2") (pin "13") (pinfunction "13_13") (pintype "passive"))
      (node (ref "SW2") (pin "2") (pinfunction "2_2") (pintype "passive"))
      (node (ref "SW3") (pin "3") (pinfunction "3_3") (pintype "passive"))
      (node (ref "SW3") (pin "4") (pinfunction "4_4") (pintype "passive"))
      (node (ref "U$1") (pin "2") (pinfunction "VSS_2") (pintype "passive"))
      (node (ref "U$2") (pin "P$10") (pinfunction "VSS1_P$10") (pintype "power_in"))
      (node (ref "U$2") (pin "P$11") (pinfunction "VSS2_P$11") (pintype "power_in"))
      (node (ref "U$2") (pin "P$12") (pinfunction "VSS3_P$12") (pintype "power_in"))
      (node (ref "U$2") (pin "P$13") (pinfunction "VSS4_P$13") (pintype "power_in"))
      (node (ref "U$2") (pin "P$14") (pinfunction "VSS5_P$14") (pintype "power_in"))
      (node (ref "U$2") (pin "P$15") (pinfunction "VSS6_P$15") (pintype "power_in"))
      (node (ref "U$2") (pin "P$6") (pinfunction "6VSS_P$6") (pintype "power_in"))
      (node (ref "U$3") (pin "2") (pinfunction "GND_2") (pintype "power_in"))
      (node (ref "U$4") (pin "2") (pinfunction "GND_2") (pintype "power_in"))
      (node (ref "U$5") (pin "GND") (pinfunction "GND_GND") (pintype "bidirectional"))
      (node (ref "U$6") (pin "3") (pinfunction "ST_3") (pintype "bidirectional"))
      (node (ref "U$6") (pin "6") (pinfunction "GND_6") (pintype "power_in"))
      (node (ref "U$6") (pin "7") (pinfunction "GND1_7") (pintype "power_in"))
      (node (ref "U$7") (pin "P$10") (pinfunction "10_VSS_P$10") (pintype "bidirectional"))
      (node (ref "U1") (pin "12") (pinfunction "VSSA_12") (pintype "power_in"))
      (node (ref "U1") (pin "18") (pinfunction "VSS_4_18") (pintype "power_in"))
      (node (ref "U1") (pin "31") (pinfunction "VSS_1_31") (pintype "power_in"))
      (node (ref "U1") (pin "47") (pinfunction "VSS_2_47") (pintype "power_in"))
      (node (ref "U1") (pin "63") (pinfunction "VSS_3_63") (pintype "power_in"))
    )
    (net (code "20") (name "KILL1") (class "Default")
      (node (ref "SV1") (pin "5") (pinfunction "5_5") (pintype "passive"))
      (node (ref "SW2") (pin "11") (pinfunction "11_11") (pintype "passive"))
    )
    (net (code "21") (name "KILL2") (class "Default")
      (node (ref "SW1") (pin "8") (pinfunction "8_8") (pintype "passive"))
      (node (ref "SW2") (pin "12") (pinfunction "12_12") (pintype "passive"))
    )
    (net (code "22") (name "KILLB2") (class "Default")
      (node (ref "SV1") (pin "4") (pinfunction "4_4") (pintype "passive"))
      (node (ref "SW1") (pin "7") (pinfunction "7_7") (pintype "passive"))
    )
    (net (code "23") (name "LED1_GR") (class "Default")
      (node (ref "R69") (pin "1") (pinfunction "1_1") (pintype "passive"))
      (node (ref "U1") (pin "4") (pinfunction "PC15_4") (pintype "bidirectional"))
    )
    (net (code "24") (name "LED1_RED") (class "Default")
      (node (ref "R56") (pin "1") (pinfunction "1_1") (pintype "passive"))
      (node (ref "U1") (pin "3") (pinfunction "PC14_3") (pintype "bidirectional"))
    )
    (net (code "25") (name "LED2_GR") (class "Default")
      (node (ref "R71") (pin "1") (pinfunction "1_1") (pintype "passive"))
      (node (ref "U1") (pin "38") (pinfunction "PC7_38") (pintype "bidirectional"))
    )
    (net (code "26") (name "LED2_RED") (class "Default")
      (node (ref "R70") (pin "1") (pinfunction "1_1") (pintype "passive"))
      (node (ref "U1") (pin "37") (pinfunction "PC6_37") (pintype "bidirectional"))
    )
    (net (code "27") (name "LED3_GR") (class "Default")
      (node (ref "R74") (pin "2") (pinfunction "2_2") (pintype "passive"))
      (node (ref "U1") (pin "61") (pinfunction "PB8_61") (pintype "bidirectional"))
    )
    (net (code "28") (name "LED3_RED") (class "Default")
      (node (ref "R75") (pin "2") (pinfunction "2_2") (pintype "passive"))
      (node (ref "U1") (pin "62") (pinfunction "PB9_62") (pintype "bidirectional"))
    )
    (net (code "29") (name "LED4_GR") (class "Default")
      (node (ref "R72") (pin "2") (pinfunction "2_2") (pintype "passive"))
      (node (ref "U1") (pin "28") (pinfunction "PB2_28") (pintype "bidirectional"))
    )
    (net (code "30") (name "LED4_RED") (class "Default")
      (node (ref "R73") (pin "2") (pinfunction "2_2") (pintype "passive"))
      (node (ref "U1") (pin "55") (pinfunction "PB3_55") (pintype "bidirectional"))
    )
    (net (code "31") (name "N$30") (class "Default")
      (node (ref "R46") (pin "2") (pinfunction "2_2") (pintype "passive"))
      (node (ref "SW3") (pin "7") (pinfunction "7_7") (pintype "passive"))
      (node (ref "SW3") (pin "8") (pinfunction "8_8") (pintype "passive"))
    )
    (net (code "32") (name "N$38") (class "Default")
      (node (ref "R47") (pin "2") (pinfunction "2_2") (pintype "passive"))
      (node (ref "SW3") (pin "10") (pinfunction "10_10") (pintype "passive"))
      (node (ref "SW3") (pin "9") (pinfunction "9_9") (pintype "passive"))
    )
    (net (code "33") (name "N$43") (class "Default")
      (node (ref "C24") (pin "1") (pinfunction "1_1") (pintype "passive"))
      (node (ref "U$6") (pin "1") (pinfunction "BYP_1") (pintype "power_in"))
    )
    (net (code "34") (name "NSWH") (class "Default")
      (node (ref "SV1") (pin "9") (pinfunction "9_9") (pintype "passive"))
      (node (ref "SW2") (pin "17") (pinfunction "17_17") (pintype "passive"))
    )
    (net (code "35") (name "Net-(C18-Pad-)") (class "Default")
      (node (ref "C18") (pin "-") (pinfunction "-_-") (pintype "passive"))
      (node (ref "D1") (pin "A") (pinfunction "A_A") (pintype "passive"))
      (node (ref "D2") (pin "C") (pinfunction "C_C") (pintype "passive"))
    )
    (net (code "36") (name "Net-(D3-PadAG)") (class "Default")
      (node (ref "D3") (pin "AG") (pinfunction "AG_AG") (pintype "passive"))
      (node (ref "Q10") (pin "C") (pinfunction "C_C") (pintype "passive"))
      (node (ref "R55") (pin "2") (pinfunction "2_2") (pintype "passive"))
    )
    (net (code "37") (name "Net-(D3-PadAR)") (class "Default")
      (node (ref "D3") (pin "AR") (pinfunction "AR_AR") (pintype "passive"))
      (node (ref "Q11") (pin "C") (pinfunction "C_C") (pintype "passive"))
      (node (ref "R52") (pin "2") (pinfunction "2_2") (pintype "passive"))
    )
    (net (code "38") (name "Net-(D4-PadAG)") (class "Default")
      (node (ref "D4") (pin "AG") (pinfunction "AG_AG") (pintype "passive"))
      (node (ref "Q12") (pin "C") (pinfunction "C_C") (pintype "passive"))
      (node (ref "R54") (pin "2") (pinfunction "2_2") (pintype "passive"))
    )
    (net (code "39") (name "Net-(D4-PadAR)") (class "Default")
      (node (ref "D4") (pin "AR") (pinfunction "AR_AR") (pintype "passive"))
      (node (ref "Q13") (pin "C") (pinfunction "C_C") (pintype "passive"))
      (node (ref "R53") (pin "2") (pinfunction "2_2") (pintype "passive"))
    )
    (net (code "40") (name "Net-(D5-PadAG)") (class "Default")
      (node (ref "D5") (pin "AG") (pinfunction "AG_AG") (pintype "passive"))
      (node (ref "Q15") (pin "C") (pinfunction "C_C") (pintype "passive"))
      (node (ref "R51") (pin "2") (pinfunction "2_2") (pintype "passive"))
    )
    (net (code "41") (name "Net-(D5-PadAR)") (class "Default")
      (node (ref "D5") (pin "AR") (pinfunction "AR_AR") (pintype "passive"))
      (node (ref "Q14") (pin "C") (pinfunction "C_C") (pintype "passive"))
      (node (ref "R10") (pin "2") (pinfunction "2_2") (pintype "passive"))
    )
    (net (code "42") (name "Net-(D6-PadAG)") (class "Default")
      (node (ref "D6") (pin "AG") (pinfunction "AG_AG") (pintype "passive"))
      (node (ref "Q9") (pin "C") (pinfunction "C_C") (pintype "passive"))
      (node (ref "R14") (pin "2") (pinfunction "2_2") (pintype "passive"))
    )
    (net (code "43") (name "Net-(D6-PadAR)") (class "Default")
      (node (ref "D6") (pin "AR") (pinfunction "AR_AR") (pintype "passive"))
      (node (ref "Q8") (pin "C") (pinfunction "C_C") (pintype "passive"))
      (node (ref "R12") (pin "2") (pinfunction "2_2") (pintype "passive"))
    )
    (net (code "44") (name "Net-(IC1A-O)") (class "Default")
      (node (ref "IC1") (pin "4") (pinfunction "O_4") (pintype "output"))
      (node (ref "U$3") (pin "3") (pinfunction "A_3") (pintype "bidirectional"))
    )
    (net (code "45") (name "Net-(IC2-DIS)") (class "Default")
      (node (ref "IC2") (pin "7") (pinfunction "DIS_7") (pintype "input"))
      (node (ref "R18") (pin "1") (pinfunction "1_1") (pintype "passive"))
      (node (ref "R20") (pin "2") (pinfunction "2_2") (pintype "passive"))
    )
    (net (code "46") (name "Net-(IC2-Q)") (class "Default")
      (node (ref "C18") (pin "+") (pinfunction "+_+") (pintype "passive"))
      (node (ref "IC2") (pin "3") (pinfunction "Q_3") (pintype "output"))
      (node (ref "R21") (pin "1") (pinfunction "1_1") (pintype "passive"))
    )
    (net (code "47") (name "Net-(IC2-THR)") (class "Default")
      (node (ref "C17") (pin "2") (pinfunction "2_2") (pintype "passive"))
      (node (ref "IC2") (pin "2") (pinfunction "TR_2") (pintype "input"))
      (node (ref "IC2") (pin "6") (pinfunction "THR_6") (pintype "input"))
      (node (ref "R20") (pin "1") (pinfunction "1_1") (pintype "passive"))
    )
    (net (code "48") (name "Net-(IC4A-+IN)") (class "Default")
      (node (ref "IC4") (pin "5") (pinfunction "+IN_5") (pintype "input"))
      (node (ref "R31") (pin "1") (pinfunction "1_1") (pintype "passive"))
      (node (ref "R32") (pin "2") (pinfunction "2_2") (pintype "passive"))
    )
    (net (code "49") (name "Net-(IC4A--IN)") (class "Default")
      (node (ref "IC4") (pin "4") (pinfunction "-IN_4") (pintype "input"))
      (node (ref "R22") (pin "1") (pinfunction "1_1") (pintype "passive"))
      (node (ref "R24") (pin "2") (pinfunction "2_2") (pintype "passive"))
    )
    (net (code "50") (name "Net-(IC4A-OUT)") (class "Default")
      (node (ref "IC4") (pin "2") (pinfunction "OUT_2") (pintype "open_collector"))
      (node (ref "R24") (pin "1") (pinfunction "1_1") (pintype "passive"))
      (node (ref "R27") (pin "1") (pinfunction "1_1") (pintype "passive"))
    )
    (net (code "51") (name "Net-(IC4B-+IN)") (class "Default")
      (node (ref "IC4") (pin "7") (pinfunction "+IN_7") (pintype "input"))
      (node (ref "R29") (pin "1") (pinfunction "1_1") (pintype "passive"))
      (node (ref "R30") (pin "2") (pinfunction "2_2") (pintype "passive"))
    )
    (net (code "52") (name "Net-(IC4B--IN)") (class "Default")
      (node (ref "IC4") (pin "6") (pinfunction "-IN_6") (pintype "input"))
      (node (ref "R22") (pin "2") (pinfunction "2_2") (pintype "passive"))
      (node (ref "R23") (pin "1") (pinfunction "1_1") (pintype "passive"))
    )
    (net (code "53") (name "Net-(IC4B-OUT)") (class "Default")
      (node (ref "IC4") (pin "1") (pinfunction "OUT_1") (pintype "open_collector"))
      (node (ref "R23") (pin "2") (pinfunction "2_2") (pintype "passive"))
      (node (ref "R25") (pin "1") (pinfunction "1_1") (pintype "passive"))
    )
    (net (code "54") (name "Net-(IC4C-+IN)") (class "Default")
      (node (ref "IC4") (pin "9") (pinfunction "+IN_9") (pintype "input"))
      (node (ref "R27") (pin "2") (pinfunction "2_2") (pintype "passive"))
      (node (ref "R28") (pin "1") (pinfunction "1_1") (pintype "passive"))
    )
    (net (code "55") (name "Net-(IC4C--IN)") (class "Default")
      (node (ref "IC4") (pin "8") (pinfunction "-IN_8") (pintype "input"))
      (node (ref "R25") (pin "2") (pinfunction "2_2") (pintype "passive"))
      (node (ref "R26") (pin "1") (pinfunction "1_1") (pintype "passive"))
    )
    (net (code "56") (name "Net-(IC4D--IN)") (class "Default")
      (node (ref "IC4") (pin "10") (pinfunction "-IN_10") (pintype "input"))
      (node (ref "IC4") (pin "13") (pinfunction "OUT_13") (pintype "open_collector"))
      (node (ref "R42") (pin "2") (pinfunction "2_2") (pintype "passive"))
    )
    (net (code "57") (name "Net-(IC5A-I)") (class "Default")
      (node (ref "IC5") (pin "2") (pinfunction "I_2") (pintype "input"))
      (node (ref "U$4") (pin "3") (pinfunction "A_3") (pintype "bidirectional"))
    )
    (net (code "58") (name "Net-(J1-Pad1)") (class "Default")
      (node (ref "J1") (pin "1") (pinfunction "1_1") (pintype "passive"))
      (node (ref "R4") (pin "2") (pinfunction "2_2") (pintype "passive"))
    )
    (net (code "59") (name "Net-(Q2-D)") (class "Default")
      (node (ref "Q2") (pin "3") (pinfunction "D_3") (pintype "passive"))
      (node (ref "SV1") (pin "10") (pinfunction "10_10") (pintype "passive"))
    )
    (net (code "60") (name "Net-(Q2-G)") (class "Default")
      (node (ref "Q2") (pin "1") (pinfunction "G_1") (pintype "passive"))
      (node (ref "Q3") (pin "C") (pinfunction "C_C") (pintype "passive"))
      (node (ref "R33") (pin "2") (pinfunction "2_2") (pintype "passive"))
    )
    (net (code "61") (name "Net-(Q3-PadB)") (class "Default")
      (node (ref "Q3") (pin "B") (pinfunction "B_B") (pintype "passive"))
      (node (ref "R34") (pin "2") (pinfunction "2_2") (pintype "passive"))
    )
    (net (code "62") (name "Net-(Q4-D)") (class "Default")
      (node (ref "Q4") (pin "3") (pinfunction "D_3") (pintype "passive"))
      (node (ref "SW2") (pin "23") (pinfunction "23_23") (pintype "passive"))
      (node (ref "SW2") (pin "24") (pinfunction "24_24") (pintype "passive"))
    )
    (net (code "63") (name "Net-(Q4-G)") (class "Default")
      (node (ref "Q4") (pin "1") (pinfunction "G_1") (pintype "passive"))
      (node (ref "Q5") (pin "C") (pinfunction "C_C") (pintype "passive"))
      (node (ref "R35") (pin "2") (pinfunction "2_2") (pintype "passive"))
    )
    (net (code "64") (name "Net-(Q5-PadB)") (class "Default")
      (node (ref "Q5") (pin "B") (pinfunction "B_B") (pintype "passive"))
      (node (ref "R36") (pin "2") (pinfunction "2_2") (pintype "passive"))
    )
    (net (code "65") (name "Net-(Q6-D)") (class "Default")
      (node (ref "Q6") (pin "3") (pinfunction "D_3") (pintype "passive"))
      (node (ref "SW1") (pin "12") (pinfunction "12_12") (pintype "passive"))
    )
    (net (code "66") (name "Net-(Q6-G)") (class "Default")
      (node (ref "Q6") (pin "1") (pinfunction "G_1") (pintype "passive"))
      (node (ref "Q7") (pin "C") (pinfunction "C_C") (pintype "passive"))
      (node (ref "R37") (pin "2") (pinfunction "2_2") (pintype "passive"))
    )
    (net (code "67") (name "Net-(Q7-PadB)") (class "Default")
      (node (ref "Q7") (pin "B") (pinfunction "B_B") (pintype "passive"))
      (node (ref "R38") (pin "2") (pinfunction "2_2") (pintype "passive"))
    )
    (net (code "68") (name "Net-(Q8-PadB)") (class "Default")
      (node (ref "Q8") (pin "B") (pinfunction "B_B") (pintype "passive"))
      (node (ref "R56") (pin "2") (pinfunction "2_2") (pintype "passive"))
    )
    (net (code "69") (name "Net-(Q9-PadB)") (class "Default")
      (node (ref "Q9") (pin "B") (pinfunction "B_B") (pintype "passive"))
      (node (ref "R69") (pin "2") (pinfunction "2_2") (pintype "passive"))
    )
    (net (code "70") (name "Net-(Q10-PadB)") (class "Default")
      (node (ref "Q10") (pin "B") (pinfunction "B_B") (pintype "passive"))
      (node (ref "R71") (pin "2") (pinfunction "2_2") (pintype "passive"))
    )
    (net (code "71") (name "Net-(Q11-PadB)") (class "Default")
      (node (ref "Q11") (pin "B") (pinfunction "B_B") (pintype "passive"))
      (node (ref "R70") (pin "2") (pinfunction "2_2") (pintype "passive"))
    )
    (net (code "72") (name "Net-(Q12-PadB)") (class "Default")
      (node (ref "Q12") (pin "B") (pinfunction "B_B") (pintype "passive"))
      (node (ref "R72") (pin "1") (pinfunction "1_1") (pintype "passive"))
    )
    (net (code "73") (name "Net-(Q13-PadB)") (class "Default")
      (node (ref "Q13") (pin "B") (pinfunction "B_B") (pintype "passive"))
      (node (ref "R73") (pin "1") (pinfunction "1_1") (pintype "passive"))
    )
    (net (code "74") (name "Net-(Q14-PadB)") (class "Default")
      (node (ref "Q14") (pin "B") (pinfunction "B_B") (pintype "passive"))
      (node (ref "R75") (pin "1") (pinfunction "1_1") (pintype "passive"))
    )
    (net (code "75") (name "Net-(Q15-PadB)") (class "Default")
      (node (ref "Q15") (pin "B") (pinfunction "B_B") (pintype "passive"))
      (node (ref "R74") (pin "1") (pinfunction "1_1") (pintype "passive"))
    )
    (net (code "76") (name "Net-(R57-Pad2)") (class "Default")
      (node (ref "R57") (pin "2") (pinfunction "2_2") (pintype "passive"))
      (node (ref "R58") (pin "1") (pinfunction "1_1") (pintype "passive"))
      (node (ref "R59") (pin "1") (pinfunction "1_1") (pintype "passive"))
    )
    (net (code "77") (name "Net-(R60-Pad2)") (class "Default")
      (node (ref "R60") (pin "2") (pinfunction "2_2") (pintype "passive"))
      (node (ref "R61") (pin "1") (pinfunction "1_1") (pintype "passive"))
      (node (ref "R62") (pin "1") (pinfunction "1_1") (pintype "passive"))
    )
    (net (code "78") (name "Net-(R63-Pad2)") (class "Default")
      (node (ref "R63") (pin "2") (pinfunction "2_2") (pintype "passive"))
      (node (ref "R64") (pin "1") (pinfunction "1_1") (pintype "passive"))
      (node (ref "R65") (pin "1") (pinfunction "1_1") (pintype "passive"))
    )
    (net (code "79") (name "Net-(R66-Pad2)") (class "Default")
      (node (ref "R66") (pin "2") (pinfunction "2_2") (pintype "passive"))
      (node (ref "R67") (pin "1") (pinfunction "1_1") (pintype "passive"))
      (node (ref "R68") (pin "1") (pinfunction "1_1") (pintype "passive"))
    )
    (net (code "80") (name "Net-(U$1-RS)") (class "Default")
      (node (ref "R1") (pin "2") (pinfunction "2_2") (pintype "passive"))
      (node (ref "U$1") (pin "8") (pinfunction "RS_8") (pintype "input"))
    )
    (net (code "81") (name "Net-(U$3-OE)") (class "Default")
      (node (ref "R45") (pin "1") (pinfunction "1_1") (pintype "passive"))
      (node (ref "U$3") (pin "5") (pinfunction "OE_5") (pintype "bidirectional"))
    )
    (net (code "82") (name "Net-(U$6-XOUT)") (class "Default")
      (node (ref "R48") (pin "1") (pinfunction "1_1") (pintype "passive"))
      (node (ref "U$6") (pin "10") (pinfunction "XOUT_10") (pintype "bidirectional"))
    )
    (net (code "83") (name "Net-(U$6-YOUT)") (class "Default")
      (node (ref "R49") (pin "1") (pinfunction "1_1") (pintype "passive"))
      (node (ref "U$6") (pin "9") (pinfunction "YOUT_9") (pintype "bidirectional"))
    )
    (net (code "84") (name "Net-(U$6-ZOUT)") (class "Default")
      (node (ref "R50") (pin "1") (pinfunction "1_1") (pintype "passive"))
      (node (ref "U$6") (pin "8") (pinfunction "ZOUT_8") (pintype "bidirectional"))
    )
    (net (code "85") (name "Net-(U1H-PD0{slash}OSC<=)") (class "Default")
      (node (ref "C9") (pin "2") (pinfunction "2_2") (pintype "passive"))
      (node (ref "Q16") (pin "1") (pinfunction "1_1") (pintype "passive"))
      (node (ref "U1") (pin "5") (pinfunction "PD0/OSC<=_5") (pintype "bidirectional"))
    )
    (net (code "86") (name "Net-(U1H-PD1{slash}OSC=>)") (class "Default")
      (node (ref "C10") (pin "1") (pinfunction "1_1") (pintype "passive"))
      (node (ref "Q16") (pin "2") (pinfunction "2_2") (pintype "passive"))
      (node (ref "U1") (pin "6") (pinfunction "PD1/OSC=>_6") (pintype "bidirectional"))
    )
    (net (code "87") (name "Net-(U1J-BOOT0)") (class "Default")
      (node (ref "R43") (pin "2") (pinfunction "2_2") (pintype "passive"))
      (node (ref "U1") (pin "60") (pinfunction "BOOT0_60") (pintype "input"))
    )
    (net (code "88") (name "OPS") (class "Default")
      (node (ref "IC7") (pin "5") (pinfunction "+IN_5") (pintype "input"))
      (node (ref "R8") (pin "2") (pinfunction "2_2") (pintype "passive"))
      (node (ref "SW2") (pin "9") (pinfunction "9_9") (pintype "passive"))
    )
    (net (code "89") (name "OPSL") (class "Default")
      (node (ref "IC7") (pin "2") (pinfunction "OUT_2") (pintype "open_collector"))
      (node (ref "IC7") (pin "4") (pinfunction "-IN_4") (pintype "input"))
      (node (ref "U1") (pin "16") (pinfunction "PA2_16") (pintype "bidirectional"))
    )
    (net (code "90") (name "REAR_ON") (class "Default")
      (node (ref "R36") (pin "1") (pinfunction "1_1") (pintype "passive"))
      (node (ref "U1") (pin "58") (pinfunction "PB6_58") (pintype "bidirectional"))
    )
    (net (code "91") (name "RPM") (class "Default")
      (node (ref "R6") (pin "2") (pinfunction "2_2") (pintype "passive"))
      (node (ref "SW2") (pin "5") (pinfunction "5_5") (pintype "passive"))
    )
    (net (code "92") (name "RPML") (class "Default")
      (node (ref "C29") (pin "2") (pinfunction "2_2") (pintype "passive"))
      (node (ref "IC7") (pin "9") (pinfunction "+IN_9") (pintype "input"))
      (node (ref "R13") (pin "2") (pinfunction "2_2") (pintype "passive"))
      (node (ref "R6") (pin "1") (pinfunction "1_1") (pintype "passive"))
    )
    (net (code "93") (name "RPMLB") (class "Default")
      (node (ref "IC7") (pin "14") (pinfunction "OUT_14") (pintype "open_collector"))
      (node (ref "IC7") (pin "8") (pinfunction "-IN_8") (pintype "input"))
      (node (ref "U1") (pin "27") (pinfunction "PB1_27") (pintype "bidirectional"))
    )
    (net (code "94") (name "RST") (class "Default")
      (node (ref "C16") (pin "2") (pinfunction "2_2") (pintype "passive"))
      (node (ref "R5") (pin "2") (pinfunction "2_2") (pintype "passive"))
      (node (ref "SW3") (pin "1") (pinfunction "1_1") (pintype "passive"))
      (node (ref "U1") (pin "7") (pinfunction "NRST_7") (pintype "input"))
    )
    (net (code "95") (name "RX") (class "Default")
      (node (ref "IC5") (pin "4") (pinfunction "O_4") (pintype "output"))
      (node (ref "U1") (pin "43") (pinfunction "PA10_43") (pintype "bidirectional"))
    )
    (net (code "96") (name "RX0") (class "Default")
      (node (ref "U$1") (pin "4") (pinfunction "RXD_4") (pintype "output"))
      (node (ref "U$4") (pin "4") (pinfunction "B_4") (pintype "bidirectional"))
    )
    (net (code "97") (name "SDIO_CLK") (class "Default")
      (node (ref "U$2") (pin "P$5") (pinfunction "5CLK_P$5") (pintype "bidirectional"))
      (node (ref "U1") (pin "53") (pinfunction "PC12_53") (pintype "bidirectional"))
    )
    (net (code "98") (name "SDIO_CMD") (class "Default")
      (node (ref "R39") (pin "1") (pinfunction "1_1") (pintype "passive"))
      (node (ref "U$2") (pin "P$3") (pinfunction "3CMD_P$3") (pintype "bidirectional"))
      (node (ref "U1") (pin "54") (pinfunction "PD2_54") (pintype "bidirectional"))
    )
    (net (code "99") (name "SDIO_D0") (class "Default")
      (node (ref "R3") (pin "1") (pinfunction "1_1") (pintype "passive"))
      (node (ref "U$2") (pin "P$7") (pinfunction "7DAT0_P$7") (pintype "bidirectional"))
      (node (ref "U1") (pin "39") (pinfunction "PC8_39") (pintype "bidirectional"))
    )
    (net (code "100") (name "SDIO_D1") (class "Default")
      (node (ref "R2") (pin "1") (pinfunction "1_1") (pintype "passive"))
      (node (ref "U$2") (pin "P$8") (pinfunction "8DAT1_P$8") (pintype "bidirectional"))
      (node (ref "U1") (pin "40") (pinfunction "PC9_40") (pintype "bidirectional"))
    )
    (net (code "101") (name "SDIO_D2") (class "Default")
      (node (ref "R41") (pin "1") (pinfunction "1_1") (pintype "passive"))
      (node (ref "U$2") (pin "P$1") (pinfunction "1DAT2_P$1") (pintype "bidirectional"))
      (node (ref "U1") (pin "51") (pinfunction "PC10_51") (pintype "bidirectional"))
    )
    (net (code "102") (name "SDIO_D3") (class "Default")
      (node (ref "R40") (pin "1") (pinfunction "1_1") (pintype "passive"))
      (node (ref "U$2") (pin "P$2") (pinfunction "2CD/DAT3_P$2") (pintype "bidirectional"))
      (node (ref "U1") (pin "52") (pinfunction "PC11_52") (pintype "bidirectional"))
    )
    (net (code "103") (name "SHD") (class "Default")
      (node (ref "SV1") (pin "6") (pinfunction "6_6") (pintype "passive"))
      (node (ref "SW2") (pin "16") (pinfunction "16_16") (pintype "passive"))
    )
    (net (code "104") (name "SHU") (class "Default")
      (node (ref "SV1") (pin "8") (pinfunction "8_8") (pintype "passive"))
      (node (ref "SW2") (pin "15") (pinfunction "15_15") (pintype "passive"))
    )
    (net (code "105") (name "STARTMOTOR1") (class "Default")
      (node (ref "K1") (pin "5") (pinfunction "O_5") (pintype "passive"))
      (node (ref "SW2") (pin "10") (pinfunction "10_10") (pintype "passive"))
    )
    (net (code "106") (name "STARTMOTOR2") (class "Default")
      (node (ref "K1") (pin "6") (pinfunction "P_6") (pintype "passive"))
      (node (ref "SW2") (pin "22") (pinfunction "22_22") (pintype "passive"))
    )
    (net (code "107") (name "STARTMOTOR3") (class "Default")
      (node (ref "K1") (pin "7") (pinfunction "S_7") (pintype "passive"))
      (node (ref "SW2") (pin "8") (pinfunction "8_8") (pintype "passive"))
    )
    (net (code "108") (name "STS1") (class "Default")
      (node (ref "R57") (pin "1") (pinfunction "1_1") (pintype "passive"))
      (node (ref "SW1") (pin "9") (pinfunction "9_9") (pintype "passive"))
    )
    (net (code "109") (name "STS1L") (class "Default")
      (node (ref "C30") (pin "1") (pinfunction "1_1") (pintype "passive"))
      (node (ref "IC6") (pin "5") (pinfunction "+IN_5") (pintype "input"))
      (node (ref "R58") (pin "2") (pinfunction "2_2") (pintype "passive"))
    )
    (net (code "110") (name "STS1LB") (class "Default")
      (node (ref "IC6") (pin "2") (pinfunction "OUT_2") (pintype "open_collector"))
      (node (ref "IC6") (pin "4") (pinfunction "-IN_4") (pintype "input"))
      (node (ref "U1") (pin "8") (pinfunction "PC0_8") (pintype "bidirectional"))
    )
    (net (code "111") (name "STS2") (class "Default")
      (node (ref "R60") (pin "1") (pinfunction "1_1") (pintype "passive"))
      (node (ref "SW1") (pin "10") (pinfunction "10_10") (pintype "passive"))
    )
    (net (code "112") (name "STS2L") (class "Default")
      (node (ref "C31") (pin "1") (pinfunction "1_1") (pintype "passive"))
      (node (ref "IC6") (pin "7") (pinfunction "+IN_7") (pintype "input"))
      (node (ref "R61") (pin "2") (pinfunction "2_2") (pintype "passive"))
    )
    (net (code "113") (name "STS2LB") (class "Default")
      (node (ref "IC6") (pin "1") (pinfunction "OUT_1") (pintype "open_collector"))
      (node (ref "IC6") (pin "6") (pinfunction "-IN_6") (pintype "input"))
      (node (ref "U1") (pin "9") (pinfunction "PC1_9") (pintype "bidirectional"))
    )
    (net (code "114") (name "STS3") (class "Default")
      (node (ref "R63") (pin "1") (pinfunction "1_1") (pintype "passive"))
      (node (ref "SW2") (pin "18") (pinfunction "18_18") (pintype "passive"))
    )
    (net (code "115") (name "STS3L") (class "Default")
      (node (ref "C32") (pin "1") (pinfunction "1_1") (pintype "passive"))
      (node (ref "IC6") (pin "9") (pinfunction "+IN_9") (pintype "input"))
      (node (ref "R64") (pin "2") (pinfunction "2_2") (pintype "passive"))
    )
    (net (code "116") (name "STS3LB") (class "Default")
      (node (ref "IC6") (pin "14") (pinfunction "OUT_14") (pintype "open_collector"))
      (node (ref "IC6") (pin "8") (pinfunction "-IN_8") (pintype "input"))
      (node (ref "U1") (pin "10") (pinfunction "PC2_10") (pintype "bidirectional"))
    )
    (net (code "117") (name "STS4") (class "Default")
      (node (ref "R66") (pin "1") (pinfunction "1_1") (pintype "passive"))
      (node (ref "SW2") (pin "19") (pinfunction "19_19") (pintype "passive"))
    )
    (net (code "118") (name "STS4L") (class "Default")
      (node (ref "C33") (pin "1") (pinfunction "1_1") (pintype "passive"))
      (node (ref "IC6") (pin "11") (pinfunction "+IN_11") (pintype "input"))
      (node (ref "R67") (pin "2") (pinfunction "2_2") (pintype "passive"))
    )
    (net (code "119") (name "STS4LB") (class "Default")
      (node (ref "IC6") (pin "10") (pinfunction "-IN_10") (pintype "input"))
      (node (ref "IC6") (pin "13") (pinfunction "OUT_13") (pintype "open_collector"))
      (node (ref "U1") (pin "11") (pinfunction "PC3_11") (pintype "bidirectional"))
    )
    (net (code "120") (name "SWCLK") (class "Default")
      (node (ref "SW3") (pin "6") (pinfunction "6_6") (pintype "passive"))
      (node (ref "U1") (pin "49") (pinfunction "PA14_49") (pintype "bidirectional"))
    )
    (net (code "121") (name "SWDIO") (class "Default")
      (node (ref "SW3") (pin "2") (pinfunction "2_2") (pintype "passive"))
      (node (ref "U1") (pin "46") (pinfunction "PA13_46") (pintype "bidirectional"))
    )
    (net (code "122") (name "SWIM") (class "Default")
      (node (ref "SW3") (pin "5") (pinfunction "5_5") (pintype "passive"))
    )
    (net (code "123") (name "TPS") (class "Default")
      (node (ref "R11") (pin "1") (pinfunction "1_1") (pintype "passive"))
      (node (ref "SW2") (pin "4") (pinfunction "4_4") (pintype "passive"))
    )
    (net (code "124") (name "TPSL") (class "Default")
      (node (ref "C36") (pin "1") (pinfunction "1_1") (pintype "passive"))
      (node (ref "IC4") (pin "11") (pinfunction "+IN_11") (pintype "input"))
      (node (ref "R11") (pin "2") (pinfunction "2_2") (pintype "passive"))
      (node (ref "R76") (pin "1") (pinfunction "1_1") (pintype "passive"))
    )
    (net (code "125") (name "TPSLB") (class "Default")
      (node (ref "R42") (pin "1") (pinfunction "1_1") (pintype "passive"))
      (node (ref "R44") (pin "2") (pinfunction "2_2") (pintype "passive"))
      (node (ref "U1") (pin "20") (pinfunction "PA4_20") (pintype "bidirectional"))
    )
    (net (code "126") (name "TX") (class "Default")
      (node (ref "IC1") (pin "2") (pinfunction "I_2") (pintype "input"))
      (node (ref "U1") (pin "42") (pinfunction "PA9_42") (pintype "bidirectional"))
    )
    (net (code "127") (name "TX0") (class "Default")
      (node (ref "U$1") (pin "1") (pinfunction "TXD_1") (pintype "input"))
      (node (ref "U$3") (pin "4") (pinfunction "B_4") (pintype "bidirectional"))
    )
    (net (code "128") (name "UART0+") (class "Default")
      (node (ref "R4") (pin "1") (pinfunction "1_1") (pintype "passive"))
      (node (ref "SV1") (pin "2") (pinfunction "2_2") (pintype "passive"))
      (node (ref "SW1") (pin "11") (pinfunction "11_11") (pintype "passive"))
      (node (ref "SW2") (pin "20") (pinfunction "20_20") (pintype "passive"))
      (node (ref "U$1") (pin "7") (pinfunction "CANH_7") (pintype "bidirectional"))
    )
    (net (code "129") (name "UART0-") (class "Default")
      (node (ref "J1") (pin "2") (pinfunction "2_2") (pintype "passive"))
      (node (ref "SV1") (pin "3") (pinfunction "3_3") (pintype "passive"))
      (node (ref "SW1") (pin "2") (pinfunction "2_2") (pintype "passive"))
      (node (ref "SW2") (pin "3") (pinfunction "3_3") (pintype "passive"))
      (node (ref "U$1") (pin "6") (pinfunction "CANL_6") (pintype "bidirectional"))
    )
    (net (code "130") (name "VBAT") (class "Default")
      (node (ref "U1") (pin "1") (pinfunction "VBAT_1") (pintype "power_in"))
    )
    (net (code "131") (name "VCC") (class "Default")
      (node (ref "C15") (pin "1") (pinfunction "1_1") (pintype "passive"))
      (node (ref "C2") (pin "1") (pinfunction "1_1") (pintype "passive"))
      (node (ref "C21") (pin "1") (pinfunction "1_1") (pintype "passive"))
      (node (ref "C23") (pin "+") (pinfunction "+_+") (pintype "passive"))
      (node (ref "C28") (pin "1") (pinfunction "1_1") (pintype "passive"))
      (node (ref "C3") (pin "1") (pinfunction "1_1") (pintype "passive"))
      (node (ref "C35") (pin "1") (pinfunction "1_1") (pintype "passive"))
      (node (ref "C37") (pin "1") (pinfunction "1_1") (pintype "passive"))
      (node (ref "C38") (pin "1") (pinfunction "1_1") (pintype "passive"))
      (node (ref "C5") (pin "1") (pinfunction "1_1") (pintype "passive"))
      (node (ref "C6") (pin "1") (pinfunction "1_1") (pintype "passive"))
      (node (ref "C7") (pin "1") (pinfunction "1_1") (pintype "passive"))
      (node (ref "C8") (pin "1") (pinfunction "1_1") (pintype "passive"))
      (node (ref "IC1") (pin "5") (pinfunction "VCC_5") (pintype "power_in"))
      (node (ref "IC5") (pin "5") (pinfunction "VCC_5") (pintype "power_in"))
      (node (ref "IC6") (pin "3") (pinfunction "V+_3") (pintype "power_in"))
      (node (ref "IC7") (pin "3") (pinfunction "V+_3") (pintype "power_in"))
      (node (ref "R10") (pin "1") (pinfunction "1_1") (pintype "passive"))
      (node (ref "R12") (pin "1") (pinfunction "1_1") (pintype "passive"))
      (node (ref "R14") (pin "1") (pinfunction "1_1") (pintype "passive"))
      (node (ref "R2") (pin "2") (pinfunction "2_2") (pintype "passive"))
      (node (ref "R3") (pin "2") (pinfunction "2_2") (pintype "passive"))
      (node (ref "R39") (pin "2") (pinfunction "2_2") (pintype "passive"))
      (node (ref "R40") (pin "2") (pinfunction "2_2") (pintype "passive"))
      (node (ref "R41") (pin "2") (pinfunction "2_2") (pintype "passive"))
      (node (ref "R46") (pin "1") (pinfunction "1_1") (pintype "passive"))
      (node (ref "R5") (pin "1") (pinfunction "1_1") (pintype "passive"))
      (node (ref "R51") (pin "1") (pinfunction "1_1") (pintype "passive"))
      (node (ref "R52") (pin "1") (pinfunction "1_1") (pintype "passive"))
      (node (ref "R53") (pin "1") (pinfunction "1_1") (pintype "passive"))
      (node (ref "R54") (pin "1") (pinfunction "1_1") (pintype "passive"))
      (node (ref "R55") (pin "1") (pinfunction "1_1") (pintype "passive"))
      (node (ref "R7") (pin "1") (pinfunction "1_1") (pintype "passive"))
      (node (ref "R8") (pin "1") (pinfunction "1_1") (pintype "passive"))
      (node (ref "U$2") (pin "P$4") (pinfunction "4VDD_P$4") (pintype "power_in"))
      (node (ref "U$3") (pin "1") (pinfunction "VCCA_1") (pintype "power_in"))
      (node (ref "U$4") (pin "1") (pinfunction "VCCA_1") (pintype "power_in"))
      (node (ref "U$4") (pin "5") (pinfunction "OE_5") (pintype "bidirectional"))
      (node (ref "U$5") (pin "VOUT") (pinfunction "VOUT_VOUT") (pintype "bidirectional"))
      (node (ref "U$6") (pin "2") (pinfunction "VDD_2") (pintype "power_in"))
      (node (ref "U$6") (pin "4") (pinfunction "EN_4") (pintype "bidirectional"))
      (node (ref "U$7") (pin "P$14") (pinfunction "14_VIO_P$14") (pintype "bidirectional"))
      (node (ref "U$7") (pin "P$2") (pinfunction "2_VCC_P$2") (pintype "bidirectional"))
      (node (ref "U1") (pin "13") (pinfunction "VDDA_13") (pintype "power_in"))
      (node (ref "U1") (pin "19") (pinfunction "VDD_4_19") (pintype "power_in"))
      (node (ref "U1") (pin "32") (pinfunction "VDD_1_32") (pintype "power_in"))
      (node (ref "U1") (pin "48") (pinfunction "VDD_2_48") (pintype "power_in"))
      (node (ref "U1") (pin "64") (pinfunction "VDD_3_64") (pintype "power_in"))
    )
    (net (code "132") (name "VCCINT") (class "Default")
      (node (ref "C12") (pin "1") (pinfunction "1_1") (pintype "passive"))
      (node (ref "C13") (pin "+") (pinfunction "+_+") (pintype "passive"))
      (node (ref "IC3") (pin "1") (pinfunction "VI_1") (pintype "input"))
      (node (ref "R19") (pin "2") (pinfunction "2_2") (pintype "passive"))
      (node (ref "R29") (pin "2") (pinfunction "2_2") (pintype "passive"))
    )
    (net (code "133") (name "VCC{slash}2") (class "Default")
      (node (ref "C1") (pin "1") (pinfunction "1_1") (pintype "passive"))
      (node (ref "C11") (pin "1") (pinfunction "1_1") (pintype "passive"))
      (node (ref "C14") (pin "+") (pinfunction "+_+") (pintype "passive"))
      (node (ref "C22") (pin "2") (pinfunction "2_2") (pintype "passive"))
      (node (ref "C4") (pin "2") (pinfunction "2_2") (pintype "passive"))
      (node (ref "IC3") (pin "3") (pinfunction "VO_3") (pintype "passive"))
      (node (ref "Q2") (pin "2") (pinfunction "S_2") (pintype "passive"))
      (node (ref "Q4") (pin "2") (pinfunction "S_2") (pintype "passive"))
      (node (ref "Q6") (pin "2") (pinfunction "S_2") (pintype "passive"))
      (node (ref "R33") (pin "1") (pinfunction "1_1") (pintype "passive"))
      (node (ref "R35") (pin "1") (pinfunction "1_1") (pintype "passive"))
      (node (ref "R37") (pin "1") (pinfunction "1_1") (pintype "passive"))
      (node (ref "R47") (pin "1") (pinfunction "1_1") (pintype "passive"))
      (node (ref "U$1") (pin "3") (pinfunction "VDD_3") (pintype "power_in"))
      (node (ref "U$3") (pin "6") (pinfunction "VCCB_6") (pintype "power_in"))
      (node (ref "U$4") (pin "6") (pinfunction "VCCB_6") (pintype "power_in"))
      (node (ref "U$5") (pin "VIN") (pinfunction "VIN_VIN") (pintype "bidirectional"))
    )
    (net (code "134") (name "WTS") (class "Default")
      (node (ref "IC7") (pin "11") (pinfunction "+IN_11") (pintype "input"))
      (node (ref "R7") (pin "2") (pinfunction "2_2") (pintype "passive"))
      (node (ref "SW2") (pin "7") (pinfunction "7_7") (pintype "passive"))
    )
    (net (code "135") (name "WTSL") (class "Default")
      (node (ref "IC7") (pin "10") (pinfunction "-IN_10") (pintype "input"))
      (node (ref "IC7") (pin "13") (pinfunction "OUT_13") (pintype "open_collector"))
      (node (ref "U1") (pin "14") (pinfunction "PA0_14") (pintype "bidirectional"))
    )
    (net (code "136") (name "XOUT") (class "Default")
      (node (ref "C27") (pin "1") (pinfunction "1_1") (pintype "passive"))
      (node (ref "R48") (pin "2") (pinfunction "2_2") (pintype "passive"))
      (node (ref "U1") (pin "21") (pinfunction "PA5_21") (pintype "bidirectional"))
    )
    (net (code "137") (name "YOUT") (class "Default")
      (node (ref "C26") (pin "1") (pinfunction "1_1") (pintype "passive"))
      (node (ref "R49") (pin "2") (pinfunction "2_2") (pintype "passive"))
      (node (ref "U1") (pin "22") (pinfunction "PA6_22") (pintype "bidirectional"))
    )
    (net (code "138") (name "ZOUT") (class "Default")
      (node (ref "C25") (pin "1") (pinfunction "1_1") (pintype "passive"))
      (node (ref "R50") (pin "2") (pinfunction "2_2") (pintype "passive"))
      (node (ref "U1") (pin "23") (pinfunction "PA7_23") (pintype "bidirectional"))
    )
    (net (code "139") (name "unconnected-(IC2-CV-Pad5)") (class "Default")
      (node (ref "IC2") (pin "5") (pinfunction "CV_5") (pintype "input"))
    )
    (net (code "140") (name "unconnected-(K1A-O-Pad2)") (class "Default")
      (node (ref "K1") (pin "2") (pinfunction "O_2") (pintype "passive"))
    )
    (net (code "141") (name "unconnected-(K1A-P-Pad3)") (class "Default")
      (node (ref "K1") (pin "3") (pinfunction "P_3") (pintype "passive"))
    )
    (net (code "142") (name "unconnected-(K1A-S-Pad4)") (class "Default")
      (node (ref "K1") (pin "4") (pinfunction "S_4") (pintype "passive"))
    )
    (net (code "143") (name "unconnected-(U$1-VREF-Pad5)") (class "Default")
      (node (ref "U$1") (pin "5") (pinfunction "VREF_5") (pintype "output"))
    )
    (net (code "144") (name "unconnected-(U$2-PadP$9)") (class "Default")
      (node (ref "U$2") (pin "P$9") (pinfunction "P$9_P$9") (pintype "no_connect"))
    )
    (net (code "145") (name "unconnected-(U$6-NC-Pad11)") (class "Default")
      (node (ref "U$6") (pin "11") (pinfunction "NC_11") (pintype "no_connect"))
    )
    (net (code "146") (name "unconnected-(U$6-NC1-Pad12)") (class "Default")
      (node (ref "U$6") (pin "12") (pinfunction "NC1_12") (pintype "no_connect"))
    )
    (net (code "147") (name "unconnected-(U$7-1_HOLD-PadP$1)") (class "Default")
      (node (ref "U$7") (pin "P$1") (pinfunction "1_HOLD_P$1") (pintype "bidirectional"))
    )
    (net (code "148") (name "unconnected-(U$7-3_RESET-PadP$3)") (class "Default")
      (node (ref "U$7") (pin "P$3") (pinfunction "3_RESET_P$3") (pintype "bidirectional"))
    )
    (net (code "149") (name "unconnected-(U$7-4_DNU-PadP$4)") (class "Default")
      (node (ref "U$7") (pin "P$4") (pinfunction "4_DNU_P$4") (pintype "bidirectional"))
    )
    (net (code "150") (name "unconnected-(U$7-5_DNU-PadP$5)") (class "Default")
      (node (ref "U$7") (pin "P$5") (pinfunction "5_DNU_P$5") (pintype "bidirectional"))
    )
    (net (code "151") (name "unconnected-(U$7-6_RFU-PadP$6)") (class "Default")
      (node (ref "U$7") (pin "P$6") (pinfunction "6_RFU_P$6") (pintype "bidirectional"))
    )
    (net (code "152") (name "unconnected-(U$7-9_WP-PadP$9)") (class "Default")
      (node (ref "U$7") (pin "P$9") (pinfunction "9_WP_P$9") (pintype "bidirectional"))
    )
    (net (code "153") (name "unconnected-(U$7-11_DNU-PadP$11)") (class "Default")
      (node (ref "U$7") (pin "P$11") (pinfunction "11_DNU_P$11") (pintype "bidirectional"))
    )
    (net (code "154") (name "unconnected-(U$7-12_DNU-PadP$12)") (class "Default")
      (node (ref "U$7") (pin "P$12") (pinfunction "12_DNU_P$12") (pintype "bidirectional"))
    )
    (net (code "155") (name "unconnected-(U$7-13_NC-PadP$13)") (class "Default")
      (node (ref "U$7") (pin "P$13") (pinfunction "13_NC_P$13") (pintype "bidirectional"))
    )
    (net (code "156") (name "unconnected-(U1B-PA8-Pad41)") (class "Default")
      (node (ref "U1") (pin "41") (pinfunction "PA8_41") (pintype "bidirectional"))
    )
    (net (code "157") (name "unconnected-(U1B-PA11-Pad44)") (class "Default")
      (node (ref "U1") (pin "44") (pinfunction "PA11_44") (pintype "bidirectional"))
    )
    (net (code "158") (name "unconnected-(U1B-PA12-Pad45)") (class "Default")
      (node (ref "U1") (pin "45") (pinfunction "PA12_45") (pintype "bidirectional"))
    )
    (net (code "159") (name "unconnected-(U1B-PA15-Pad50)") (class "Default")
      (node (ref "U1") (pin "50") (pinfunction "PA15_50") (pintype "bidirectional"))
    )
    (net (code "160") (name "unconnected-(U1C-PA1-Pad15)") (class "Default")
      (node (ref "U1") (pin "15") (pinfunction "PA1_15") (pintype "bidirectional"))
    )
    (net (code "161") (name "unconnected-(U1D-PB10-Pad29)") (class "Default")
      (node (ref "U1") (pin "29") (pinfunction "PB10_29") (pintype "bidirectional"))
    )
    (net (code "162") (name "unconnected-(U1D-PB12-Pad33)") (class "Default")
      (node (ref "U1") (pin "33") (pinfunction "PB12_33") (pintype "bidirectional"))
    )
    (net (code "163") (name "unconnected-(U1E-PB4-Pad56)") (class "Default")
      (node (ref "U1") (pin "56") (pinfunction "PB4_56") (pintype "bidirectional"))
    )
  )
)
